# HOMER3E-V3_5-G510.net
KiCad netlist of a schematic drawn in Altium Designer
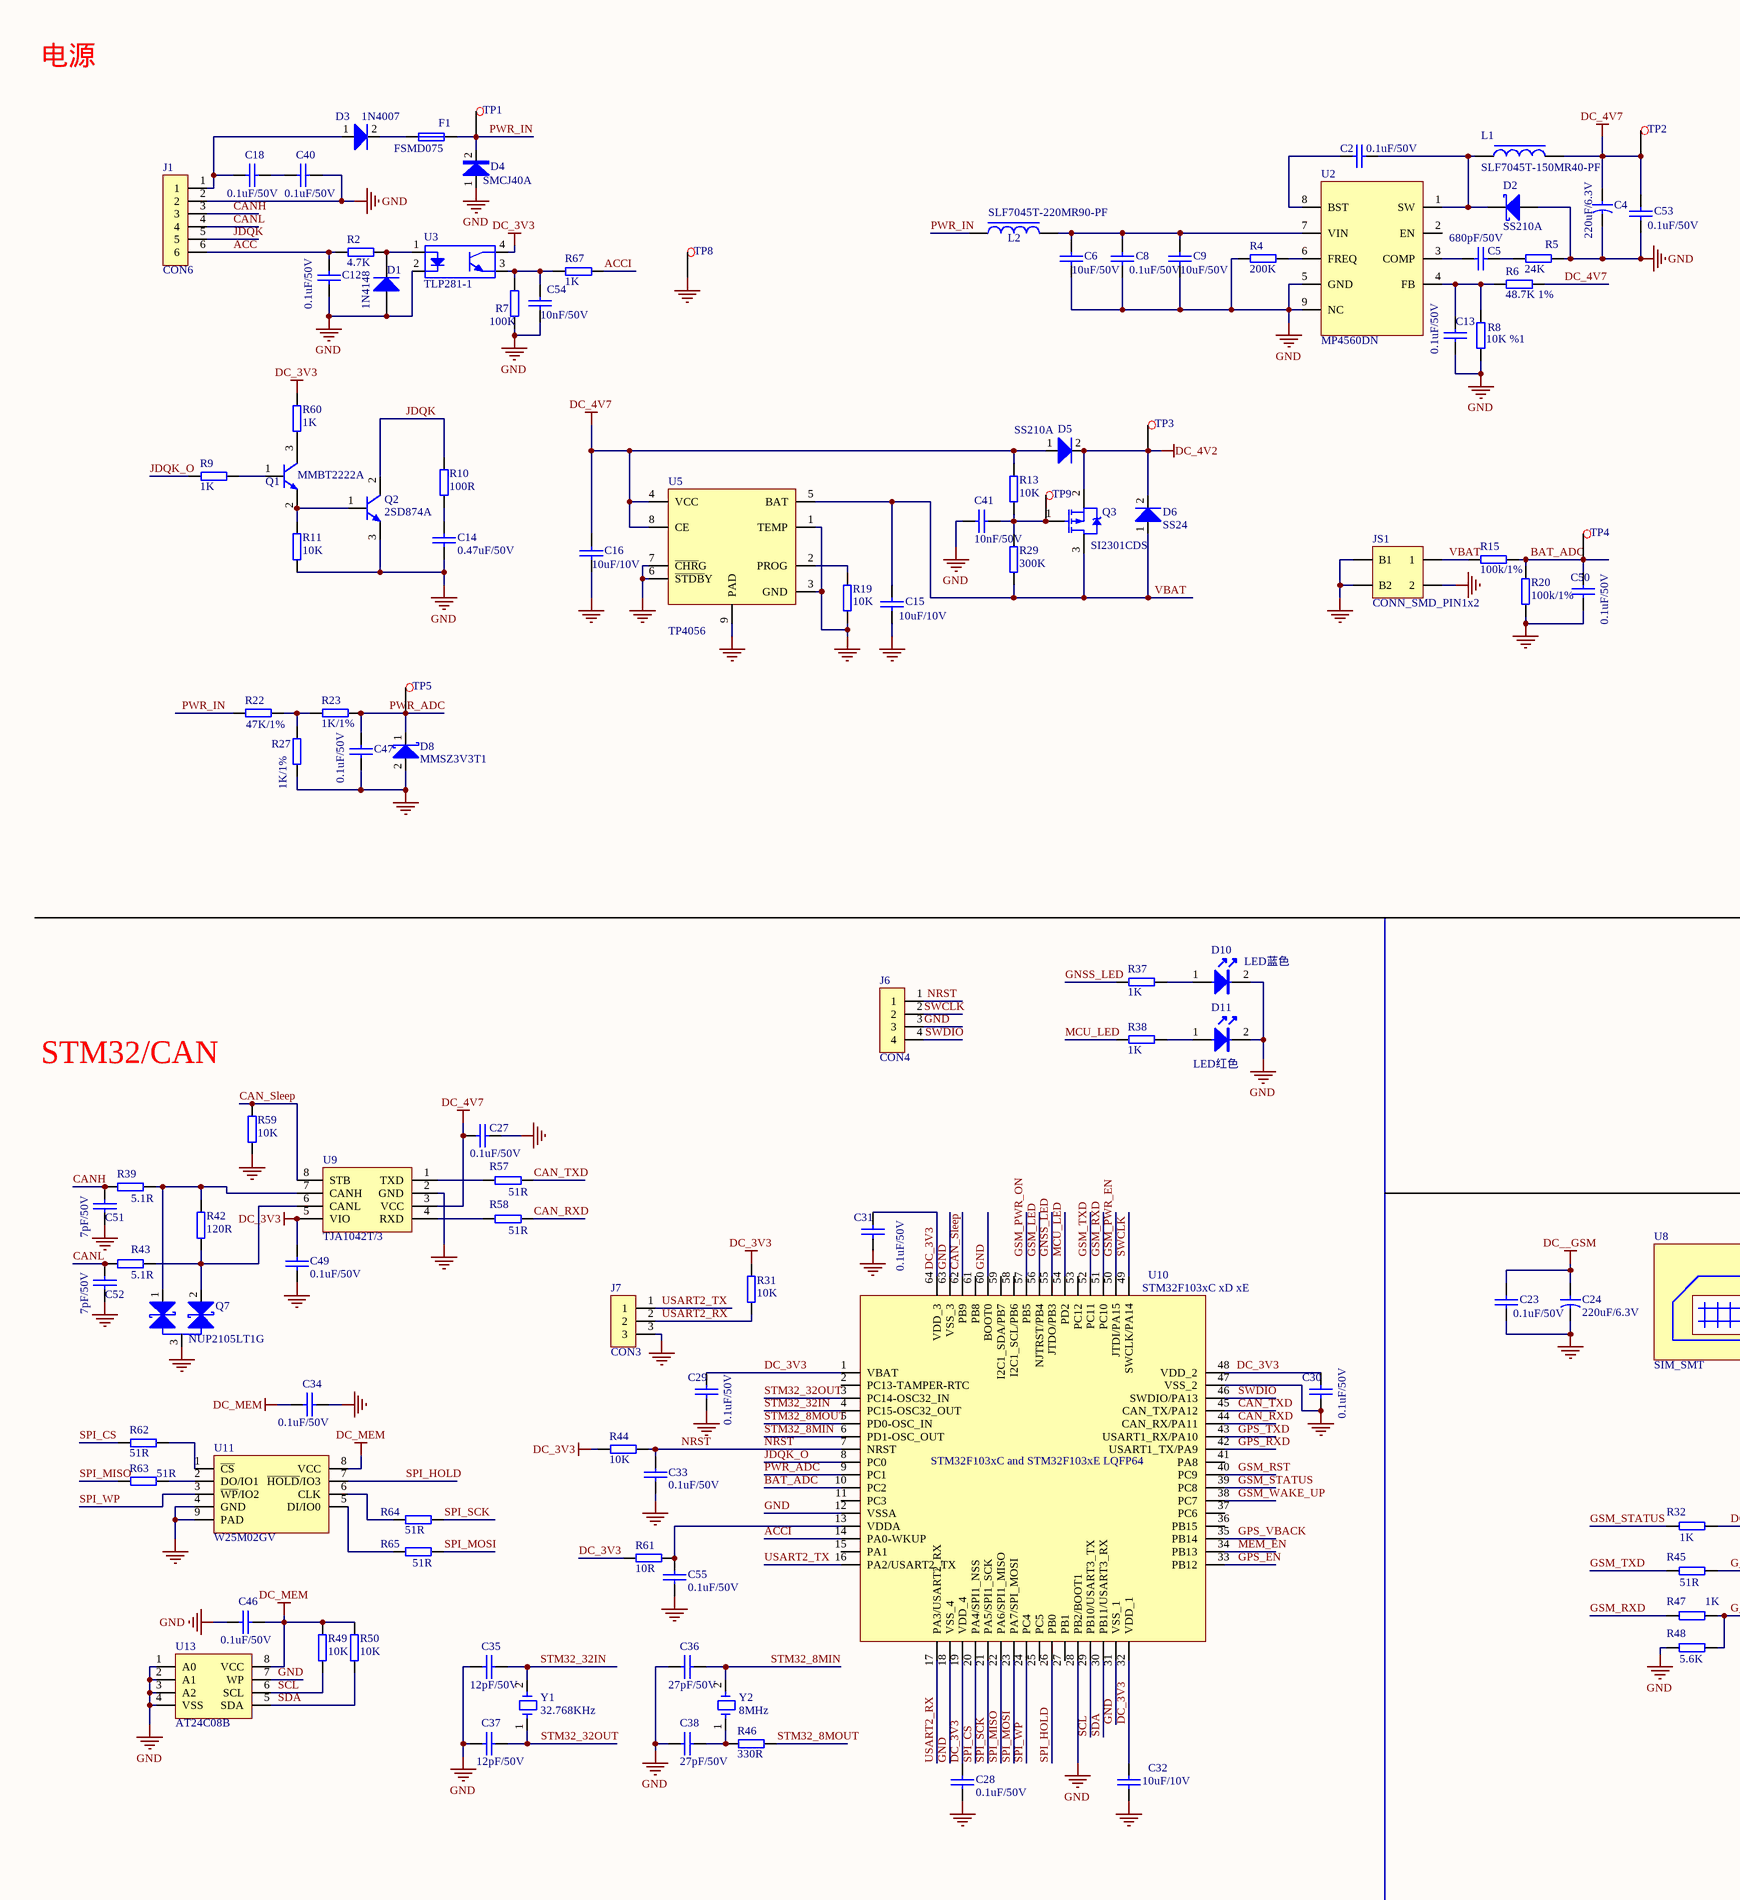
[diagram p0: HOMER3E-V3.5-G510.SchDoc, left]
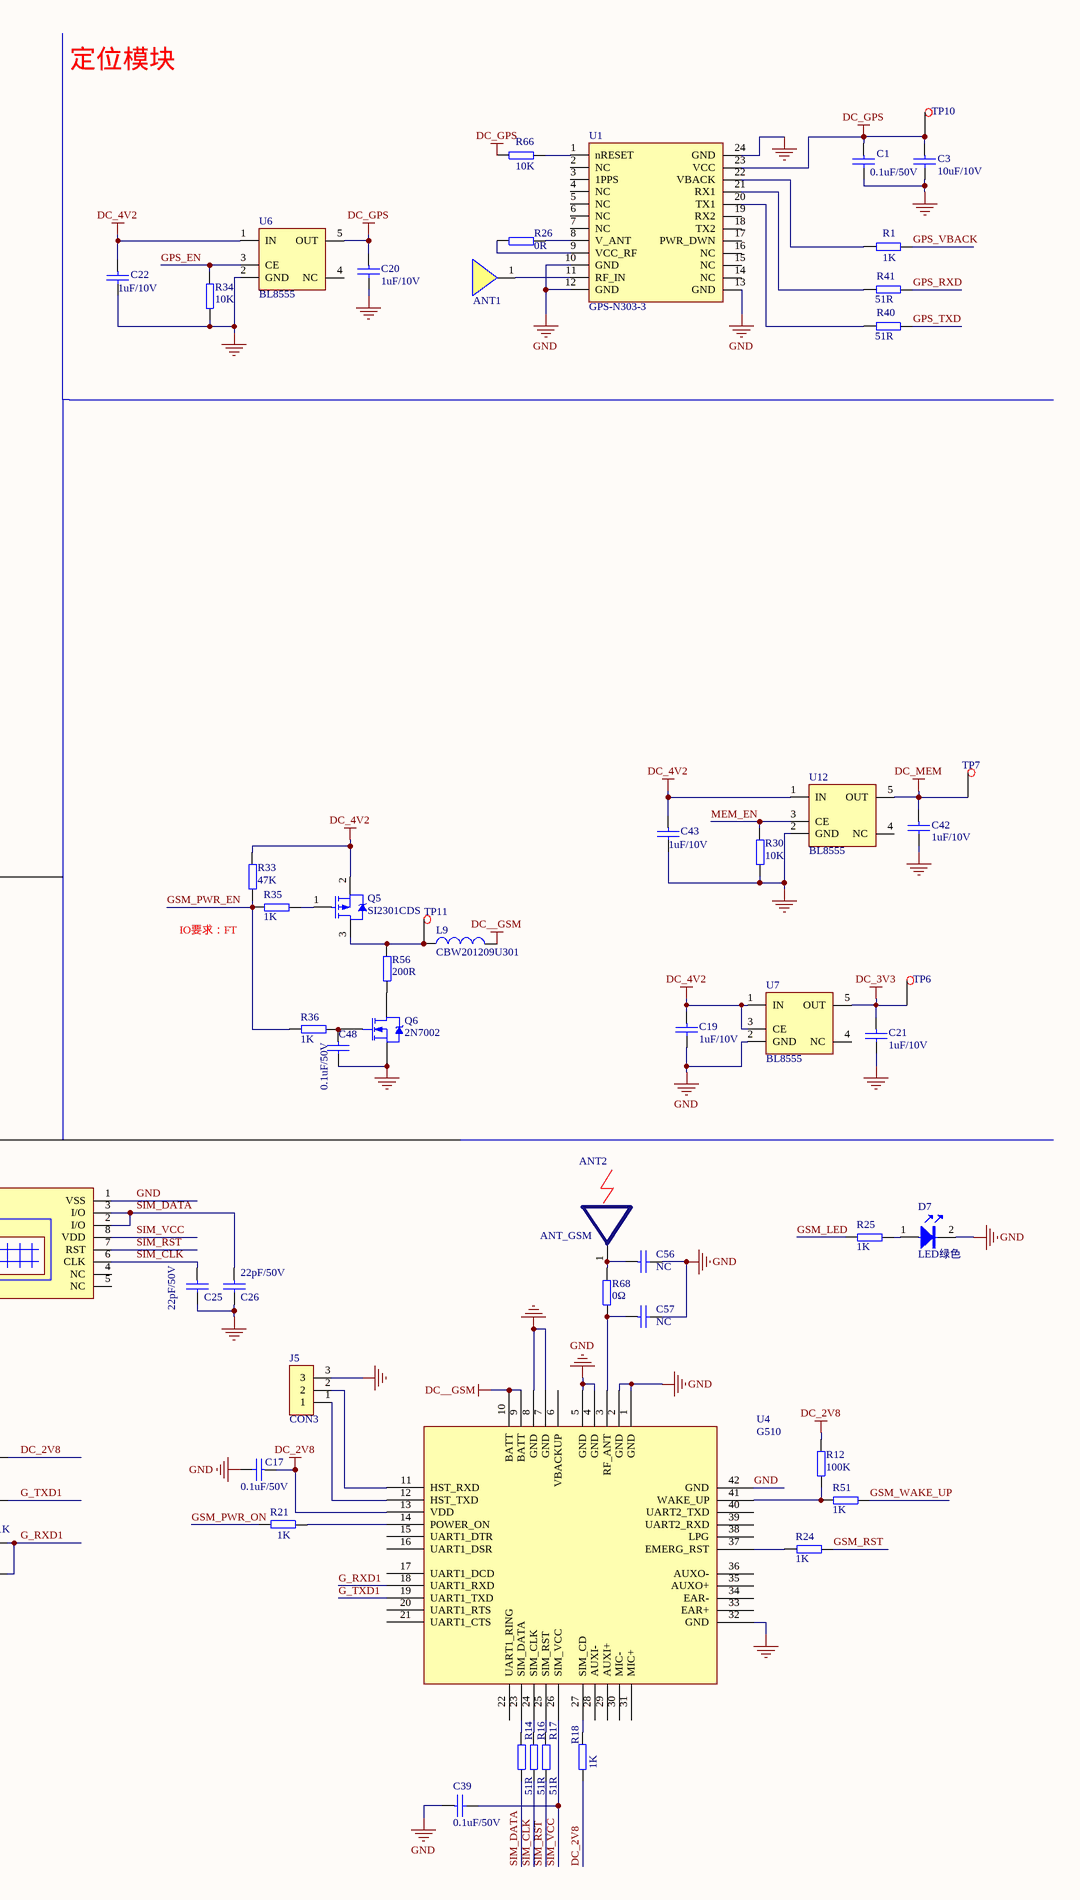
[diagram p1: HOMER3E-V3.5-G510.SchDoc, right]

(export (version "E")
  (design (tool "Eeschema 10.0.6"))
  (components
    (comp (ref "ANT1") (value "ANT") (footprint "GPS_ANT_25*25") (libsource (lib "AltiumLib") (part "ANT")))
    (comp (ref "ANT2") (value "ANT_GSM") (footprint "GSM_ANT") (libsource (lib "AltiumLib") (part "ANT_GSM")))
    (comp (ref "C1")
      (value "0.1uF/50V")
      (footprint "0603")
      (description "Capacitor")
      (libsource (lib "AltiumLib") (part "CAP"))
    )
    (comp (ref "C2")
      (value "0.1uF/50V")
      (footprint "0603")
      (description "Capacitor")
      (libsource (lib "AltiumLib") (part "CAP"))
    )
    (comp (ref "C3")
      (value "10uF/10V")
      (footprint "0603")
      (description "Capacitor")
      (libsource (lib "AltiumLib") (part "CAP"))
    )
    (comp (ref "C4")
      (value "220uF/6.3V")
      (footprint "7343")
      (description "Capacitor")
      (libsource (lib "AltiumLib") (part "Cap1"))
    )
    (comp (ref "C5")
      (value "680pF/50V")
      (footprint "0603")
      (description "Capacitor")
      (libsource (lib "AltiumLib") (part "CAP"))
    )
    (comp (ref "C6")
      (value "10uF/50V")
      (footprint "1206")
      (description "Capacitor")
      (libsource (lib "AltiumLib") (part "CAP"))
    )
    (comp (ref "C8")
      (value "0.1uF/50V")
      (footprint "0805")
      (description "Capacitor")
      (libsource (lib "AltiumLib") (part "CAP"))
    )
    (comp (ref "C9")
      (value "10uF/50V")
      (footprint "1206")
      (description "Capacitor")
      (libsource (lib "AltiumLib") (part "CAP"))
    )
    (comp (ref "C12")
      (value "0.1uF/50V")
      (footprint "0805")
      (description "Capacitor")
      (libsource (lib "AltiumLib") (part "CAP"))
    )
    (comp (ref "C13")
      (value "0.1uF/50V")
      (footprint "0603")
      (description "Capacitor")
      (libsource (lib "AltiumLib") (part "CAP"))
    )
    (comp (ref "C14")
      (value "0.47uF/50V")
      (footprint "0805")
      (description "Capacitor")
      (libsource (lib "AltiumLib") (part "CAP"))
    )
    (comp (ref "C15")
      (value "10uF/10V")
      (footprint "0603")
      (description "Capacitor")
      (libsource (lib "AltiumLib") (part "CAP"))
    )
    (comp (ref "C16")
      (value "10uF/10V")
      (footprint "0603")
      (description "Capacitor")
      (libsource (lib "AltiumLib") (part "CAP"))
    )
    (comp (ref "C17")
      (value "0.1uF/50V")
      (footprint "0603")
      (description "Capacitor")
      (libsource (lib "AltiumLib") (part "CAP"))
    )
    (comp (ref "C18")
      (value "0.1uF/50V")
      (footprint "0805")
      (description "Capacitor")
      (libsource (lib "AltiumLib") (part "CAP"))
    )
    (comp (ref "C19")
      (value "1uF/10V")
      (footprint "0603")
      (description "Capacitor")
      (libsource (lib "AltiumLib") (part "CAP"))
    )
    (comp (ref "C20")
      (value "1uF/10V")
      (footprint "0603")
      (description "Capacitor")
      (libsource (lib "AltiumLib") (part "CAP"))
    )
    (comp (ref "C21")
      (value "1uF/10V")
      (footprint "0603")
      (description "Capacitor")
      (libsource (lib "AltiumLib") (part "CAP"))
    )
    (comp (ref "C22")
      (value "1uF/10V")
      (footprint "0603")
      (description "Capacitor")
      (libsource (lib "AltiumLib") (part "CAP"))
    )
    (comp (ref "C23")
      (value "0.1uF/50V")
      (footprint "0603")
      (description "Capacitor")
      (libsource (lib "AltiumLib") (part "CAP"))
    )
    (comp (ref "C24")
      (value "220uF/6.3V")
      (footprint "7343")
      (description "Capacitor")
      (libsource (lib "AltiumLib") (part "Cap1"))
    )
    (comp (ref "C25")
      (value "22pF/50V")
      (footprint "0603")
      (description "Capacitor")
      (libsource (lib "AltiumLib") (part "CAP"))
    )
    (comp (ref "C26")
      (value "22pF/50V")
      (footprint "0603")
      (description "Capacitor")
      (libsource (lib "AltiumLib") (part "CAP"))
    )
    (comp (ref "C27")
      (value "0.1uF/50V")
      (footprint "0603")
      (description "Capacitor")
      (libsource (lib "AltiumLib") (part "CAP"))
    )
    (comp (ref "C28")
      (value "0.1uF/50V")
      (footprint "0603")
      (description "Capacitor")
      (libsource (lib "AltiumLib") (part "CAP"))
    )
    (comp (ref "C29")
      (value "0.1uF/50V")
      (footprint "0603")
      (description "Capacitor")
      (libsource (lib "AltiumLib") (part "CAP"))
    )
    (comp (ref "C30")
      (value "0.1uF/50V")
      (footprint "0603")
      (description "Capacitor")
      (libsource (lib "AltiumLib") (part "CAP"))
    )
    (comp (ref "C31")
      (value "0.1uF/50V")
      (footprint "0603")
      (description "Capacitor")
      (libsource (lib "AltiumLib") (part "CAP"))
    )
    (comp (ref "C32")
      (value "10uF/10V")
      (footprint "0603")
      (description "Capacitor")
      (libsource (lib "AltiumLib") (part "CAP"))
    )
    (comp (ref "C33")
      (value "0.1uF/50V")
      (footprint "0603")
      (description "Capacitor")
      (libsource (lib "AltiumLib") (part "CAP"))
    )
    (comp (ref "C34")
      (value "0.1uF/50V")
      (footprint "0603")
      (description "Capacitor")
      (libsource (lib "AltiumLib") (part "CAP"))
    )
    (comp (ref "C35")
      (value "12pF/50V")
      (footprint "0603")
      (description "Capacitor")
      (libsource (lib "AltiumLib") (part "CAP"))
    )
    (comp (ref "C36")
      (value "27pF/50V")
      (footprint "0603")
      (description "Capacitor")
      (libsource (lib "AltiumLib") (part "CAP"))
    )
    (comp (ref "C37")
      (value "12pF/50V")
      (footprint "0603")
      (description "Capacitor")
      (libsource (lib "AltiumLib") (part "CAP"))
    )
    (comp (ref "C38")
      (value "27pF/50V")
      (footprint "0603")
      (description "Capacitor")
      (libsource (lib "AltiumLib") (part "CAP"))
    )
    (comp (ref "C39")
      (value "0.1uF/50V")
      (footprint "0603")
      (description "Capacitor")
      (libsource (lib "AltiumLib") (part "CAP"))
    )
    (comp (ref "C40")
      (value "0.1uF/50V")
      (footprint "0805")
      (description "Capacitor")
      (libsource (lib "AltiumLib") (part "CAP"))
    )
    (comp (ref "C41")
      (value "10nF/50V")
      (footprint "0603")
      (description "Capacitor")
      (libsource (lib "AltiumLib") (part "CAP"))
    )
    (comp (ref "C42")
      (value "1uF/10V")
      (footprint "0603")
      (description "Capacitor")
      (libsource (lib "AltiumLib") (part "CAP"))
    )
    (comp (ref "C43")
      (value "1uF/10V")
      (footprint "0603")
      (description "Capacitor")
      (libsource (lib "AltiumLib") (part "CAP"))
    )
    (comp (ref "C46")
      (value "0.1uF/50V")
      (footprint "0603")
      (description "Capacitor")
      (libsource (lib "AltiumLib") (part "CAP"))
    )
    (comp (ref "C47")
      (value "0.1uF/50V")
      (footprint "0603")
      (description "Capacitor")
      (libsource (lib "AltiumLib") (part "CAP"))
    )
    (comp (ref "C48")
      (value "0.1uF/50V")
      (footprint "0603")
      (description "Capacitor")
      (libsource (lib "*") (part "CAP"))
    )
    (comp (ref "C49")
      (value "0.1uF/50V")
      (footprint "0603")
      (description "Capacitor")
      (libsource (lib "AltiumLib") (part "CAP"))
    )
    (comp (ref "C50")
      (value "0.1uF/50V")
      (footprint "0603")
      (description "Capacitor")
      (libsource (lib "AltiumLib") (part "CAP"))
    )
    (comp (ref "C51")
      (value "7pF/50V")
      (footprint "0603")
      (description "Capacitor")
      (libsource (lib "*") (part "CAP"))
    )
    (comp (ref "C52")
      (value "7pF/50V")
      (footprint "0603")
      (description "Capacitor")
      (libsource (lib "*") (part "CAP"))
    )
    (comp (ref "C53")
      (value "0.1uF/50V")
      (footprint "0603")
      (description "Capacitor")
      (libsource (lib "AltiumLib") (part "CAP"))
    )
    (comp (ref "C54")
      (value "10nF/50V")
      (footprint "0603")
      (description "Capacitor")
      (libsource (lib "AltiumLib") (part "CAP"))
    )
    (comp (ref "C55")
      (value "0.1uF/50V")
      (footprint "0603")
      (description "Capacitor")
      (libsource (lib "AltiumLib") (part "CAP"))
    )
    (comp (ref "C56")
      (value "NC")
      (footprint "C0603")
      (description "Capacitor")
      (libsource (lib "AltiumLib") (part "CAP"))
    )
    (comp (ref "C57")
      (value "NC")
      (footprint "C0603")
      (description "Capacitor")
      (libsource (lib "AltiumLib") (part "CAP"))
    )
    (comp (ref "D1")
      (value "1N4148")
      (footprint "SOD-123")
      (description "Default Diode")
      (fields (field (name "PUBLISHER") "Altium Limited"))
      (libsource (lib "Miscellaneous Devices") (part "Diode"))
    )
    (comp (ref "D2")
      (value "SS210A")
      (footprint "DO-214AC")
      (description "Schottky Diode")
      (libsource (lib "AltiumLib") (part "B340A"))
    )
    (comp (ref "D3")
      (value "1N4007")
      (footprint "DO-214AC")
      (description "High Conductance Fast Diode")
      (libsource (lib "AltiumLib") (part "1N4007"))
    )
    (comp (ref "D4") (value "SMCJ40A") (footprint "SMCJ40A") (libsource (lib "AltiumLib") (part "SMCJ40A")))
    (comp (ref "D5")
      (value "SS210A")
      (footprint "DO-214AC")
      (description "High Conductance Fast Diode")
      (libsource (lib "AltiumLib") (part "1N4007"))
    )
    (comp (ref "D6")
      (value "SS24")
      (footprint "DO-214AC")
      (description "High Conductance Fast Diode")
      (libsource (lib "AltiumLib") (part "1N4007"))
    )
    (comp (ref "D7")
      (value "LED绿色")
      (footprint "0603_led")
      (description "LED")
      (libsource (lib "AltiumLib") (part "LED"))
    )
    (comp (ref "D8")
      (value "MMSZ3V3T1")
      (footprint "SOD-123")
      (description "TVS")
      (libsource (lib "AltiumLib") (part "MMSZ3V3T1"))
    )
    (comp (ref "D10")
      (value "LED蓝色")
      (footprint "0603_led")
      (description "LED")
      (libsource (lib "AltiumLib") (part "LED"))
    )
    (comp (ref "D11")
      (value "LED红色")
      (footprint "0603_led")
      (description "LED")
      (libsource (lib "AltiumLib") (part "LED"))
    )
    (comp (ref "F1")
      (value "FSMD075")
      (footprint "2920")
      (description "Fuse")
      (libsource (lib "AltiumLib") (part "Fuse"))
    )
    (comp (ref "J1") (value "CON6") (footprint "CON6") (libsource (lib "AltiumLib") (part "CON6")))
    (comp (ref "J5") (value "CON3") (footprint "PH-3(2.54)") (libsource (lib "") (part "CON3_1")))
    (comp (ref "J6") (value "CON4") (footprint "PH-4(2.54)") (libsource (lib "AltiumLib") (part "CON4")))
    (comp (ref "J7") (value "CON3") (footprint "PH-3(2.54)") (libsource (lib "AltiumLib") (part "CON3")))
    (comp (ref "JS1")
      (value "CONN_SMD_PIN1x2")
      (footprint "MOLEX_53261-0271")
      (libsource (lib "AltiumLib") (part "CONN_SMD_PIN1x2"))
    )
    (comp (ref "L1")
      (value "SLF7045T-150MR40-PF")
      (footprint "MURATA_7 X 7")
      (description "INDUCTOR")
      (libsource (lib "AltiumLib") (part "INDUCTOR_2"))
    )
    (comp (ref "L2")
      (value "SLF7045T-220MR90-PF")
      (footprint "MURATA_7 X 7")
      (description "Magnetic-Core Inductor")
      (libsource (lib "AltiumLib") (part "Inductor"))
    )
    (comp (ref "L9")
      (value "CBW201209U301")
      (footprint "0805")
      (description "Inductor")
      (fields (field (name "PUBLISHER") "Altium Limited"))
      (libsource (lib "*") (part "Inductor"))
    )
    (comp (ref "Q1")
      (value "MMBT2222A")
      (footprint "SOT23-3")
      (libsource (lib "AltiumLib") (part "MMBT2222A"))
    )
    (comp (ref "Q2")
      (value "2SD874A")
      (footprint "SOT-89-3L")
      (description "NPN General Purpose Amplifier")
      (libsource (lib "AltiumLib") (part "2SD874"))
    )
    (comp (ref "Q3")
      (value "SI2301CDS")
      (footprint "SOT23-3")
      (description "P-Channel Power MOSFET")
      (libsource (lib "AltiumLib") (part "AO3415A"))
    )
    (comp (ref "Q5") (value "SI2301CDS") (footprint "SOT23-3") (libsource (lib "*") (part "Si2301ADS")))
    (comp (ref "Q6")
      (value "2N7002")
      (footprint "SOT23-3")
      (description "N-Channel Power MOSFET")
      (fields (field (name "PUBLISHER") "Altium Limited"))
      (libsource (lib "*") (part "NMOS-2"))
    )
    (comp (ref "Q7")
      (value "NUP2105LT1G")
      (footprint "SOT23-3")
      (libsource (lib "AltiumLib") (part "NUP2105LT1G"))
    )
    (comp (ref "R1")
      (value "1K")
      (footprint "0603")
      (description "Resistor")
      (libsource (lib "AltiumLib") (part "Res"))
    )
    (comp (ref "R2")
      (value "4.7K")
      (footprint "0603")
      (description "Resistor")
      (libsource (lib "AltiumLib") (part "Res"))
    )
    (comp (ref "R4")
      (value "200K")
      (footprint "0603")
      (description "Resistor")
      (libsource (lib "AltiumLib") (part "Res"))
    )
    (comp (ref "R5")
      (value "24K")
      (footprint "0603")
      (description "Resistor")
      (libsource (lib "AltiumLib") (part "Res"))
    )
    (comp (ref "R6")
      (value "48.7K 1%")
      (footprint "0603")
      (description "Resistor")
      (libsource (lib "AltiumLib") (part "Res"))
    )
    (comp (ref "R7")
      (value "100K")
      (footprint "0603")
      (description "Resistor")
      (libsource (lib "AltiumLib") (part "Res"))
    )
    (comp (ref "R8")
      (value "10K %1")
      (footprint "0603")
      (description "Resistor")
      (libsource (lib "AltiumLib") (part "Res"))
    )
    (comp (ref "R9")
      (value "1K")
      (footprint "0603")
      (description "Resistor")
      (libsource (lib "AltiumLib") (part "Res"))
    )
    (comp (ref "R10")
      (value "100R")
      (footprint "0805")
      (description "Resistor")
      (libsource (lib "AltiumLib") (part "Res"))
    )
    (comp (ref "R11")
      (value "10K")
      (footprint "0603")
      (description "Resistor")
      (libsource (lib "AltiumLib") (part "Res"))
    )
    (comp (ref "R12")
      (value "100K")
      (footprint "0603")
      (description "Resistor")
      (libsource (lib "AltiumLib") (part "Res"))
    )
    (comp (ref "R13")
      (value "10K")
      (footprint "0603")
      (description "Resistor")
      (libsource (lib "AltiumLib") (part "Res"))
    )
    (comp (ref "R14")
      (value "51R")
      (footprint "0603")
      (description "Resistor")
      (libsource (lib "AltiumLib") (part "Res"))
    )
    (comp (ref "R15")
      (value "100k/1%")
      (footprint "0603")
      (description "Resistor")
      (libsource (lib "AltiumLib") (part "Res"))
    )
    (comp (ref "R16")
      (value "51R")
      (footprint "0603")
      (description "Resistor")
      (libsource (lib "AltiumLib") (part "Res"))
    )
    (comp (ref "R17")
      (value "51R")
      (footprint "0603")
      (description "Resistor")
      (libsource (lib "AltiumLib") (part "Res"))
    )
    (comp (ref "R18") (value "1K") (footprint "0603") (libsource (lib "*") (part "RES_0603")))
    (comp (ref "R19")
      (value "10K")
      (footprint "0603")
      (description "Resistor")
      (libsource (lib "AltiumLib") (part "Res"))
    )
    (comp (ref "R20")
      (value "100k/1%")
      (footprint "0603")
      (description "Resistor")
      (libsource (lib "AltiumLib") (part "Res"))
    )
    (comp (ref "R21")
      (value "1K")
      (footprint "0603")
      (description "Resistor")
      (libsource (lib "AltiumLib") (part "Res"))
    )
    (comp (ref "R22")
      (value "47K/1%")
      (footprint "0603")
      (description "Resistor")
      (libsource (lib "AltiumLib") (part "Res"))
    )
    (comp (ref "R23")
      (value "1K/1%")
      (footprint "0603")
      (description "Resistor")
      (libsource (lib "AltiumLib") (part "Res"))
    )
    (comp (ref "R24")
      (value "1K")
      (footprint "0603")
      (description "Resistor")
      (libsource (lib "AltiumLib") (part "Res"))
    )
    (comp (ref "R25")
      (value "1K")
      (footprint "0603")
      (description "Resistor")
      (libsource (lib "AltiumLib") (part "Res"))
    )
    (comp (ref "R26")
      (value "0R")
      (footprint "0603")
      (description "Resistor")
      (libsource (lib "AltiumLib") (part "Res"))
    )
    (comp (ref "R27")
      (value "1K/1%")
      (footprint "0603")
      (description "Resistor")
      (libsource (lib "AltiumLib") (part "Res"))
    )
    (comp (ref "R29")
      (value "300K")
      (footprint "0603")
      (description "Resistor")
      (libsource (lib "AltiumLib") (part "Res"))
    )
    (comp (ref "R30")
      (value "10K")
      (footprint "0603")
      (description "Resistor")
      (libsource (lib "AltiumLib") (part "Res"))
    )
    (comp (ref "R31")
      (value "10K")
      (footprint "0603")
      (description "Resistor")
      (libsource (lib "AltiumLib") (part "Res"))
    )
    (comp (ref "R32")
      (value "1K")
      (footprint "0603")
      (description "Resistor")
      (libsource (lib "AltiumLib") (part "Res"))
    )
    (comp (ref "R33")
      (value "47K")
      (footprint "0603")
      (description "Resistor")
      (libsource (lib "*") (part "Res"))
    )
    (comp (ref "R34")
      (value "10K")
      (footprint "0603")
      (description "Resistor")
      (libsource (lib "AltiumLib") (part "Res"))
    )
    (comp (ref "R35")
      (value "1K")
      (footprint "0603")
      (description "Resistor")
      (libsource (lib "*") (part "Res"))
    )
    (comp (ref "R36")
      (value "1K")
      (footprint "0603")
      (description "Resistor")
      (libsource (lib "*") (part "Res"))
    )
    (comp (ref "R37")
      (value "1K")
      (footprint "0603")
      (description "Resistor")
      (libsource (lib "AltiumLib") (part "Res"))
    )
    (comp (ref "R38")
      (value "1K")
      (footprint "0603")
      (description "Resistor")
      (libsource (lib "AltiumLib") (part "Res"))
    )
    (comp (ref "R39")
      (value "5.1R")
      (footprint "0603")
      (description "Resistor")
      (libsource (lib "AltiumLib") (part "Res"))
    )
    (comp (ref "R40")
      (value "51R")
      (footprint "0603")
      (description "Resistor")
      (libsource (lib "AltiumLib") (part "Res"))
    )
    (comp (ref "R41")
      (value "51R")
      (footprint "0603")
      (description "Resistor")
      (libsource (lib "AltiumLib") (part "Res"))
    )
    (comp (ref "R42")
      (value "120R")
      (footprint "0805")
      (description "Resistor")
      (libsource (lib "AltiumLib") (part "Res"))
    )
    (comp (ref "R43")
      (value "5.1R")
      (footprint "0603")
      (description "Resistor")
      (libsource (lib "AltiumLib") (part "Res"))
    )
    (comp (ref "R44")
      (value "10K")
      (footprint "0603")
      (description "Resistor")
      (libsource (lib "AltiumLib") (part "Res"))
    )
    (comp (ref "R45")
      (value "51R")
      (footprint "0603")
      (description "Resistor")
      (libsource (lib "AltiumLib") (part "Res"))
    )
    (comp (ref "R46")
      (value "330R")
      (footprint "0603")
      (description "Resistor")
      (libsource (lib "AltiumLib") (part "Res"))
    )
    (comp (ref "R47")
      (value "1K")
      (footprint "0603")
      (description "Resistor")
      (libsource (lib "AltiumLib") (part "Res"))
    )
    (comp (ref "R48")
      (value "5.6K")
      (footprint "0603")
      (description "Resistor")
      (libsource (lib "AltiumLib") (part "Res"))
    )
    (comp (ref "R49")
      (value "10K")
      (footprint "0603")
      (description "Resistor")
      (libsource (lib "AltiumLib") (part "Res"))
    )
    (comp (ref "R50")
      (value "10K")
      (footprint "0603")
      (description "Resistor")
      (libsource (lib "AltiumLib") (part "Res"))
    )
    (comp (ref "R51")
      (value "1K")
      (footprint "0603")
      (description "Resistor")
      (libsource (lib "AltiumLib") (part "Res"))
    )
    (comp (ref "R56")
      (value "200R")
      (footprint "0805")
      (description "Resistor")
      (libsource (lib "*") (part "Res"))
    )
    (comp (ref "R57")
      (value "51R")
      (footprint "0603")
      (description "Resistor")
      (libsource (lib "AltiumLib") (part "Res"))
    )
    (comp (ref "R58")
      (value "51R")
      (footprint "0603")
      (description "Resistor")
      (libsource (lib "AltiumLib") (part "Res"))
    )
    (comp (ref "R59")
      (value "10K")
      (footprint "0603")
      (description "Resistor")
      (libsource (lib "AltiumLib") (part "Res"))
    )
    (comp (ref "R60")
      (value "1K")
      (footprint "0603")
      (description "Resistor")
      (libsource (lib "AltiumLib") (part "Res"))
    )
    (comp (ref "R61")
      (value "10R")
      (footprint "0603")
      (description "Resistor")
      (libsource (lib "AltiumLib") (part "Res"))
    )
    (comp (ref "R62")
      (value "51R")
      (footprint "0603")
      (description "Resistor")
      (libsource (lib "AltiumLib") (part "Res"))
    )
    (comp (ref "R63")
      (value "51R")
      (footprint "0603")
      (description "Resistor")
      (libsource (lib "AltiumLib") (part "Res"))
    )
    (comp (ref "R64")
      (value "51R")
      (footprint "0603")
      (description "Resistor")
      (libsource (lib "AltiumLib") (part "Res"))
    )
    (comp (ref "R65")
      (value "51R")
      (footprint "0603")
      (description "Resistor")
      (libsource (lib "AltiumLib") (part "Res"))
    )
    (comp (ref "R66")
      (value "10K")
      (footprint "0603")
      (description "Resistor")
      (libsource (lib "AltiumLib") (part "Res"))
    )
    (comp (ref "R67")
      (value "1K")
      (footprint "0603")
      (description "Resistor")
      (libsource (lib "AltiumLib") (part "Res"))
    )
    (comp (ref "R68")
      (value "0Ω")
      (footprint "R0603")
      (description "Resistor")
      (libsource (lib "AltiumLib") (part "Res"))
    )
    (comp (ref "TP1")
      (value "TestPoint")
      (footprint "TESTPOINT")
      (libsource (lib "AD SCH器件库") (part "TestPoint"))
    )
    (comp (ref "TP2")
      (value "TestPoint")
      (footprint "TESTPOINT")
      (libsource (lib "AD SCH器件库") (part "TestPoint"))
    )
    (comp (ref "TP3")
      (value "TestPoint")
      (footprint "TESTPOINT")
      (libsource (lib "AD SCH器件库") (part "TestPoint"))
    )
    (comp (ref "TP4")
      (value "TestPoint")
      (footprint "TESTPOINT")
      (libsource (lib "AD SCH器件库") (part "TestPoint"))
    )
    (comp (ref "TP5")
      (value "TestPoint")
      (footprint "TESTPOINT")
      (libsource (lib "AD SCH器件库") (part "TestPoint"))
    )
    (comp (ref "TP6")
      (value "TestPoint")
      (footprint "TESTPOINT")
      (libsource (lib "AD SCH器件库") (part "TestPoint"))
    )
    (comp (ref "TP7")
      (value "TestPoint")
      (footprint "TESTPOINT")
      (libsource (lib "AD SCH器件库") (part "TestPoint"))
    )
    (comp (ref "TP8")
      (value "TestPoint")
      (footprint "TESTPOINT")
      (libsource (lib "AD SCH器件库") (part "TestPoint"))
    )
    (comp (ref "TP9")
      (value "TestPoint")
      (footprint "TESTPOINT")
      (libsource (lib "AD SCH器件库") (part "TestPoint"))
    )
    (comp (ref "TP10") (value "TestPoint") (libsource (lib "AD SCH器件库") (part "TestPoint")))
    (comp (ref "TP11") (value "TestPoint") (libsource (lib "AD SCH器件库") (part "TestPoint")))
    (comp (ref "U1")
      (value "GPS-N303-3")
      (footprint "N303-3")
      (libsource (lib "AD SCH器件库") (part "GPS-N303-3"))
    )
    (comp (ref "U2")
      (value "MP4560DN")
      (footprint "MP4560DN_FOOTPRINT")
      (libsource (lib "AltiumLib") (part "MP4560DN"))
    )
    (comp (ref "U3")
      (value "TLP281-1")
      (footprint "tlp281")
      (description "光电耦合器")
      (libsource (lib "AltiumLib") (part "TLP281-1"))
    )
    (comp (ref "U4") (value "G510") (footprint "G510-Q50-20") (libsource (lib "AltiumLib") (part "G510")))
    (comp (ref "U5")
      (value "TP4056")
      (footprint "MP4560DN_FOOTPRINT")
      (libsource (lib "AltiumLib") (part "TP4056"))
    )
    (comp (ref "U6") (value "BL8555") (footprint "SOT23-5") (libsource (lib "AltiumLib") (part "BL8555")))
    (comp (ref "U7") (value "BL8555") (footprint "SOT23-5") (libsource (lib "AltiumLib") (part "BL8555")))
    (comp (ref "U8") (value "SIM_SMT") (footprint "SIM_SMT") (libsource (lib "AltiumLib") (part "SIM_SMT")))
    (comp (ref "U9") (value "TJA1042T/3") (footprint "SO-8") (libsource (lib "器件库") (part "TJA1042T/3")))
    (comp (ref "U10")
      (value "STM32F103xC xD xE")
      (footprint "TQFP-64")
      (libsource (lib "AltiumLib") (part "STM32F103xC xD xE"))
    )
    (comp (ref "U11")
      (value "W25M02GV")
      (footprint "WSON8X6-8")
      (libsource (lib "AltiumLib") (part "W25M02GV"))
    )
    (comp (ref "U12") (value "BL8555") (footprint "SOT23-5") (libsource (lib "AltiumLib") (part "BL8555")))
    (comp (ref "U13")
      (value "AT24C08B")
      (footprint "SO-8")
      (description "8K I2C CMOS Serial EEPROM")
      (libsource (lib "AltiumLib") (part "AT24C08B"))
    )
    (comp (ref "Y1")
      (value "32.768KHz")
      (footprint "XTAL_FC-135")
      (description "Crystal Oscillator")
      (libsource (lib "AltiumLib") (part "XTAL"))
    )
    (comp (ref "Y2")
      (value "8MHz")
      (footprint "XTAL_5032_2")
      (description "Crystal Oscillator")
      (libsource (lib "AltiumLib") (part "XTAL"))
    )
  )
  (nets
    (net (code "1") (name "/ACC") (class "Default")
      (node (ref "C12") (pin "1") (pinfunction "1_1") (pintype "passive"))
      (node (ref "J1") (pin "6") (pinfunction "6_6") (pintype "passive"))
      (node (ref "R2") (pin "2") (pinfunction "2_2") (pintype "passive"))
    )
    (net (code "2") (name "/ACCI") (class "Default")
      (node (ref "R67") (pin "2") (pinfunction "2_2") (pintype "passive"))
      (node (ref "U10") (pin "14") (pinfunction "PA0-WKUP_14") (pintype "passive"))
    )
    (net (code "3") (name "/BAT_ADC") (class "Default")
      (node (ref "C50") (pin "1") (pinfunction "1_1") (pintype "passive"))
      (node (ref "R15") (pin "1") (pinfunction "1_1") (pintype "passive"))
      (node (ref "R20") (pin "1") (pinfunction "1_1") (pintype "passive"))
      (node (ref "TP4") (pin "1") (pinfunction "1_1") (pintype "passive"))
      (node (ref "U10") (pin "10") (pinfunction "PC2_10") (pintype "passive"))
    )
    (net (code "4") (name "/CANH") (class "Default")
      (node (ref "C51") (pin "1") (pinfunction "1_1") (pintype "passive"))
      (node (ref "J1") (pin "3") (pinfunction "3_3") (pintype "passive"))
      (node (ref "R39") (pin "2") (pinfunction "2_2") (pintype "passive"))
    )
    (net (code "5") (name "/CANL") (class "Default")
      (node (ref "C52") (pin "1") (pinfunction "1_1") (pintype "passive"))
      (node (ref "J1") (pin "4") (pinfunction "4_4") (pintype "passive"))
      (node (ref "R43") (pin "2") (pinfunction "2_2") (pintype "passive"))
    )
    (net (code "6") (name "/CAN_RXD") (class "Default")
      (node (ref "R58") (pin "2") (pinfunction "2_2") (pintype "passive"))
      (node (ref "U10") (pin "44") (pinfunction "CAN_RX/PA11_44") (pintype "passive"))
    )
    (net (code "7") (name "/CAN_Sleep") (class "Default")
      (node (ref "R59") (pin "1") (pinfunction "1_1") (pintype "passive"))
      (node (ref "U10") (pin "62") (pinfunction "PB9_62") (pintype "passive"))
      (node (ref "U9") (pin "8") (pinfunction "STB_8") (pintype "passive"))
    )
    (net (code "8") (name "/CAN_TXD") (class "Default")
      (node (ref "R57") (pin "2") (pinfunction "2_2") (pintype "passive"))
      (node (ref "U10") (pin "45") (pinfunction "CAN_TX/PA12_45") (pintype "passive"))
    )
    (net (code "9") (name "/GNSS_LED") (class "Default")
      (node (ref "R37") (pin "1") (pinfunction "1_1") (pintype "passive"))
      (node (ref "U10") (pin "55") (pinfunction "JTDO/PB3_55") (pintype "passive"))
    )
    (net (code "10") (name "/GPS_EN") (class "Default")
      (node (ref "R34") (pin "1") (pinfunction "1_1") (pintype "passive"))
      (node (ref "U10") (pin "33") (pinfunction "PB12_33") (pintype "passive"))
      (node (ref "U6") (pin "3") (pinfunction "CE_3") (pintype "passive"))
    )
    (net (code "11") (name "/GPS_RXD") (class "Default")
      (node (ref "R41") (pin "1") (pinfunction "1_1") (pintype "passive"))
      (node (ref "U10") (pin "42") (pinfunction "USART1_TX/PA9_42") (pintype "passive"))
    )
    (net (code "12") (name "/GPS_TXD") (class "Default")
      (node (ref "R40") (pin "1") (pinfunction "1_1") (pintype "passive"))
      (node (ref "U10") (pin "43") (pinfunction "USART1_RX/PA10_43") (pintype "passive"))
    )
    (net (code "13") (name "/GPS_VBACK") (class "Default")
      (node (ref "R1") (pin "1") (pinfunction "1_1") (pintype "passive"))
      (node (ref "U10") (pin "35") (pinfunction "PB14_35") (pintype "passive"))
    )
    (net (code "14") (name "/GSM_LED") (class "Default")
      (node (ref "R25") (pin "1") (pinfunction "1_1") (pintype "passive"))
      (node (ref "U10") (pin "56") (pinfunction "NJTRST/PB4_56") (pintype "passive"))
    )
    (net (code "15") (name "/GSM_PWR_EN") (class "Default")
      (node (ref "R33") (pin "2") (pinfunction "2_2") (pintype "passive"))
      (node (ref "R35") (pin "1") (pinfunction "1_1") (pintype "passive"))
      (node (ref "R36") (pin "2") (pinfunction "2_2") (pintype "passive"))
      (node (ref "U10") (pin "50") (pinfunction "JTDI/PA15_50") (pintype "passive"))
    )
    (net (code "16") (name "/GSM_PWR_ON") (class "Default")
      (node (ref "R21") (pin "2") (pinfunction "2_2") (pintype "passive"))
      (node (ref "U10") (pin "57") (pinfunction "PB5_57") (pintype "passive"))
    )
    (net (code "17") (name "/GSM_RST") (class "Default")
      (node (ref "R24") (pin "2") (pinfunction "2_2") (pintype "passive"))
      (node (ref "U10") (pin "40") (pinfunction "PC9_40") (pintype "passive"))
    )
    (net (code "18") (name "/GSM_RXD") (class "Default")
      (node (ref "R47") (pin "2") (pinfunction "2_2") (pintype "passive"))
      (node (ref "U10") (pin "51") (pinfunction "PC10_51") (pintype "passive"))
    )
    (net (code "19") (name "/GSM_STATUS") (class "Default")
      (node (ref "R32") (pin "2") (pinfunction "2_2") (pintype "passive"))
      (node (ref "U10") (pin "39") (pinfunction "PC8_39") (pintype "passive"))
    )
    (net (code "20") (name "/GSM_TXD") (class "Default")
      (node (ref "R45") (pin "2") (pinfunction "2_2") (pintype "passive"))
      (node (ref "U10") (pin "52") (pinfunction "PC11_52") (pintype "passive"))
    )
    (net (code "21") (name "/GSM_WAKE_UP") (class "Default")
      (node (ref "R51") (pin "2") (pinfunction "2_2") (pintype "passive"))
      (node (ref "U10") (pin "38") (pinfunction "PC7_38") (pintype "passive"))
    )
    (net (code "22") (name "/G_RXD1") (class "Default")
      (node (ref "R47") (pin "1") (pinfunction "1_1") (pintype "passive"))
      (node (ref "R48") (pin "1") (pinfunction "1_1") (pintype "passive"))
      (node (ref "U4") (pin "18") (pinfunction "UART1_RXD_18") (pintype "passive"))
    )
    (net (code "23") (name "/G_TXD1") (class "Default")
      (node (ref "R45") (pin "1") (pinfunction "1_1") (pintype "passive"))
      (node (ref "U4") (pin "19") (pinfunction "UART1_TXD_19") (pintype "passive"))
    )
    (net (code "24") (name "/JDQK") (class "Default")
      (node (ref "J1") (pin "5") (pinfunction "5_5") (pintype "passive"))
      (node (ref "Q2") (pin "2") (pinfunction "B_2") (pintype "passive"))
      (node (ref "R10") (pin "1") (pinfunction "1_1") (pintype "passive"))
    )
    (net (code "25") (name "/JDQK_O") (class "Default")
      (node (ref "R9") (pin "1") (pinfunction "1_1") (pintype "passive"))
      (node (ref "U10") (pin "8") (pinfunction "PC0_8") (pintype "passive"))
    )
    (net (code "26") (name "/MCU_LED") (class "Default")
      (node (ref "R38") (pin "2") (pinfunction "2_2") (pintype "passive"))
      (node (ref "U10") (pin "54") (pinfunction "PD2_54") (pintype "passive"))
    )
    (net (code "27") (name "/MEM_EN") (class "Default")
      (node (ref "R30") (pin "1") (pinfunction "1_1") (pintype "passive"))
      (node (ref "U10") (pin "34") (pinfunction "PB13_34") (pintype "passive"))
      (node (ref "U12") (pin "3") (pinfunction "CE_3") (pintype "passive"))
    )
    (net (code "28") (name "/NRST") (class "Default")
      (node (ref "C33") (pin "1") (pinfunction "1_1") (pintype "passive"))
      (node (ref "J6") (pin "1") (pinfunction "1_1") (pintype "passive"))
      (node (ref "R44") (pin "1") (pinfunction "1_1") (pintype "passive"))
      (node (ref "U10") (pin "7") (pinfunction "NRST_7") (pintype "passive"))
    )
    (net (code "29") (name "/PWR_ADC") (class "Default")
      (node (ref "C47") (pin "1") (pinfunction "1_1") (pintype "passive"))
      (node (ref "D8") (pin "1") (pinfunction "K_1") (pintype "passive"))
      (node (ref "R23") (pin "1") (pinfunction "1_1") (pintype "passive"))
      (node (ref "TP5") (pin "1") (pinfunction "1_1") (pintype "passive"))
      (node (ref "U10") (pin "9") (pinfunction "PC1_9") (pintype "passive"))
    )
    (net (code "30") (name "/PWR_IN") (class "Default")
      (node (ref "D4") (pin "2") (pinfunction "K_2") (pintype "passive"))
      (node (ref "F1") (pin "2") (pinfunction "2_2") (pintype "passive"))
      (node (ref "L2") (pin "1") (pinfunction "1_1") (pintype "passive"))
      (node (ref "R22") (pin "2") (pinfunction "2_2") (pintype "passive"))
      (node (ref "TP1") (pin "1") (pinfunction "1_1") (pintype "passive"))
    )
    (net (code "31") (name "/SCL") (class "Default")
      (node (ref "R49") (pin "2") (pinfunction "2_2") (pintype "passive"))
      (node (ref "U10") (pin "29") (pinfunction "PB10/USART3_TX_29") (pintype "passive"))
      (node (ref "U13") (pin "6") (pinfunction "SCL_6") (pintype "passive"))
    )
    (net (code "32") (name "/SDA") (class "Default")
      (node (ref "R50") (pin "2") (pinfunction "2_2") (pintype "passive"))
      (node (ref "U10") (pin "30") (pinfunction "PB11/USART3_RX_30") (pintype "passive"))
      (node (ref "U13") (pin "5") (pinfunction "SDA_5") (pintype "passive"))
    )
    (net (code "33") (name "/SIM_CLK") (class "Default")
      (node (ref "C25") (pin "1") (pinfunction "1_1") (pintype "passive"))
      (node (ref "R16") (pin "2") (pinfunction "2_2") (pintype "passive"))
      (node (ref "U8") (pin "6") (pinfunction "CLK_6") (pintype "passive"))
    )
    (net (code "34") (name "/SIM_DATA") (class "Default")
      (node (ref "C26") (pin "1") (pinfunction "1_1") (pintype "passive"))
      (node (ref "R14") (pin "2") (pinfunction "2_2") (pintype "passive"))
      (node (ref "U8") (pin "2") (pinfunction "I/O_2") (pintype "passive"))
      (node (ref "U8") (pin "3") (pinfunction "I/O_3") (pintype "passive"))
    )
    (net (code "35") (name "/SIM_RST") (class "Default")
      (node (ref "R17") (pin "2") (pinfunction "2_2") (pintype "passive"))
      (node (ref "U8") (pin "7") (pinfunction "RST_7") (pintype "passive"))
    )
    (net (code "36") (name "/SIM_VCC") (class "Default")
      (node (ref "C39") (pin "2") (pinfunction "2_2") (pintype "passive"))
      (node (ref "U4") (pin "26") (pinfunction "SIM_VCC_26") (pintype "passive"))
      (node (ref "U8") (pin "8") (pinfunction "VDD_8") (pintype "passive"))
    )
    (net (code "37") (name "/SPI_CS") (class "Default")
      (node (ref "R62") (pin "1") (pinfunction "1_1") (pintype "passive"))
      (node (ref "U10") (pin "20") (pinfunction "PA4/SPI1_NSS_20") (pintype "passive"))
    )
    (net (code "38") (name "/SPI_HOLD") (class "Default")
      (node (ref "U10") (pin "26") (pinfunction "PB0_26") (pintype "passive"))
      (node (ref "U11") (pin "7") (pinfunction "~{HOLD}/IO3_7") (pintype "passive"))
    )
    (net (code "39") (name "/SPI_MISO") (class "Default")
      (node (ref "R63") (pin "1") (pinfunction "1_1") (pintype "passive"))
      (node (ref "U10") (pin "22") (pinfunction "PA6/SPI1_MISO_22") (pintype "passive"))
    )
    (net (code "40") (name "/SPI_MOSI") (class "Default")
      (node (ref "R65") (pin "2") (pinfunction "2_2") (pintype "passive"))
      (node (ref "U10") (pin "23") (pinfunction "PA7/SPI_MOSI_23") (pintype "passive"))
    )
    (net (code "41") (name "/SPI_SCK") (class "Default")
      (node (ref "R64") (pin "2") (pinfunction "2_2") (pintype "passive"))
      (node (ref "U10") (pin "21") (pinfunction "PA5/SPI1_SCK_21") (pintype "passive"))
    )
    (net (code "42") (name "/SPI_WP") (class "Default")
      (node (ref "U10") (pin "24") (pinfunction "PC4_24") (pintype "passive"))
      (node (ref "U11") (pin "3") (pinfunction "~{WP}/IO2_3") (pintype "passive"))
    )
    (net (code "43") (name "/STM32_8MIN") (class "Default")
      (node (ref "C36") (pin "2") (pinfunction "2_2") (pintype "passive"))
      (node (ref "U10") (pin "6") (pinfunction "PD1-OSC_OUT_6") (pintype "passive"))
      (node (ref "Y2") (pin "2") (pinfunction "OSC2_2") (pintype "passive"))
    )
    (net (code "44") (name "/STM32_8MOUT") (class "Default")
      (node (ref "R46") (pin "2") (pinfunction "2_2") (pintype "passive"))
      (node (ref "U10") (pin "5") (pinfunction "PD0-OSC_IN_5") (pintype "passive"))
    )
    (net (code "45") (name "/STM32_32IN") (class "Default")
      (node (ref "C35") (pin "2") (pinfunction "2_2") (pintype "passive"))
      (node (ref "U10") (pin "4") (pinfunction "PC15-OSC32_OUT_4") (pintype "passive"))
      (node (ref "Y1") (pin "2") (pinfunction "OSC2_2") (pintype "passive"))
    )
    (net (code "46") (name "/STM32_32OUT") (class "Default")
      (node (ref "C37") (pin "2") (pinfunction "2_2") (pintype "passive"))
      (node (ref "U10") (pin "3") (pinfunction "PC14-OSC32_IN_3") (pintype "passive"))
      (node (ref "Y1") (pin "1") (pinfunction "OSC1_1") (pintype "passive"))
    )
    (net (code "47") (name "/SWCLK") (class "Default")
      (node (ref "J6") (pin "2") (pinfunction "2_2") (pintype "passive"))
      (node (ref "U10") (pin "49") (pinfunction "SWCLK/PA14_49") (pintype "passive"))
    )
    (net (code "48") (name "/SWDIO") (class "Default")
      (node (ref "J6") (pin "4") (pinfunction "4_4") (pintype "passive"))
      (node (ref "U10") (pin "46") (pinfunction "SWDIO/PA13_46") (pintype "passive"))
    )
    (net (code "49") (name "/USART2_RX") (class "Default")
      (node (ref "J7") (pin "2") (pinfunction "2_2") (pintype "passive"))
      (node (ref "R31") (pin "2") (pinfunction "2_2") (pintype "passive"))
      (node (ref "U10") (pin "17") (pinfunction "PA3/USART2_RX_17") (pintype "passive"))
    )
    (net (code "50") (name "/USART2_TX") (class "Default")
      (node (ref "J7") (pin "1") (pinfunction "1_1") (pintype "passive"))
      (node (ref "U10") (pin "16") (pinfunction "PA2/USART2_TX_16") (pintype "passive"))
    )
    (net (code "51") (name "/VBAT") (class "Default")
      (node (ref "C15") (pin "1") (pinfunction "1_1") (pintype "passive"))
      (node (ref "D6") (pin "1") (pinfunction "A_1") (pintype "passive"))
      (node (ref "JS1") (pin "1") (pinfunction "1_1") (pintype "passive"))
      (node (ref "Q3") (pin "3") (pinfunction "S_3") (pintype "passive"))
      (node (ref "R15") (pin "2") (pinfunction "2_2") (pintype "passive"))
      (node (ref "R29") (pin "2") (pinfunction "2_2") (pintype "passive"))
      (node (ref "U5") (pin "5") (pinfunction "BAT_5") (pintype "passive"))
    )
    (net (code "52") (name "DC_2V8") (class "Default")
      (node (ref "C17") (pin "1") (pinfunction "1_1") (pintype "passive"))
      (node (ref "R12") (pin "1") (pinfunction "1_1") (pintype "passive"))
      (node (ref "R18") (pin "1") (pintype "passive"))
      (node (ref "R32") (pin "1") (pinfunction "1_1") (pintype "passive"))
      (node (ref "U4") (pin "13") (pinfunction "VDD_13") (pintype "passive"))
    )
    (net (code "53") (name "DC_3V3") (class "Default")
      (node (ref "C21") (pin "1") (pinfunction "1_1") (pintype "passive"))
      (node (ref "C28") (pin "1") (pinfunction "1_1") (pintype "passive"))
      (node (ref "C29") (pin "1") (pinfunction "1_1") (pintype "passive"))
      (node (ref "C30") (pin "1") (pinfunction "1_1") (pintype "passive"))
      (node (ref "C31") (pin "1") (pinfunction "1_1") (pintype "passive"))
      (node (ref "C32") (pin "1") (pinfunction "1_1") (pintype "passive"))
      (node (ref "C49") (pin "2") (pinfunction "2_2") (pintype "passive"))
      (node (ref "R31") (pin "1") (pinfunction "1_1") (pintype "passive"))
      (node (ref "R44") (pin "2") (pinfunction "2_2") (pintype "passive"))
      (node (ref "R60") (pin "2") (pinfunction "2_2") (pintype "passive"))
      (node (ref "R61") (pin "2") (pinfunction "2_2") (pintype "passive"))
      (node (ref "TP6") (pin "1") (pinfunction "1_1") (pintype "passive"))
      (node (ref "U10") (pin "1") (pinfunction "VBAT_1") (pintype "passive"))
      (node (ref "U10") (pin "19") (pinfunction "VDD_4_19") (pintype "passive"))
      (node (ref "U10") (pin "32") (pinfunction "VDD_1_32") (pintype "passive"))
      (node (ref "U10") (pin "48") (pinfunction "VDD_2_48") (pintype "passive"))
      (node (ref "U10") (pin "64") (pinfunction "VDD_3_64") (pintype "passive"))
      (node (ref "U3") (pin "4") (pinfunction "4_4") (pintype "passive"))
      (node (ref "U7") (pin "5") (pinfunction "OUT_5") (pintype "passive"))
      (node (ref "U9") (pin "5") (pinfunction "VIO_5") (pintype "passive"))
    )
    (net (code "54") (name "DC_4V2") (class "Default")
      (node (ref "C19") (pin "1") (pinfunction "1_1") (pintype "passive"))
      (node (ref "C22") (pin "1") (pinfunction "1_1") (pintype "passive"))
      (node (ref "C43") (pin "1") (pinfunction "1_1") (pintype "passive"))
      (node (ref "D5") (pin "2") (pinfunction "K_2") (pintype "passive"))
      (node (ref "D6") (pin "2") (pinfunction "K_2") (pintype "passive"))
      (node (ref "Q3") (pin "2") (pinfunction "D_2") (pintype "passive"))
      (node (ref "Q5") (pin "2") (pinfunction "D_2") (pintype "passive"))
      (node (ref "R33") (pin "1") (pinfunction "1_1") (pintype "passive"))
      (node (ref "TP3") (pin "1") (pinfunction "1_1") (pintype "passive"))
      (node (ref "U12") (pin "1") (pinfunction "IN_1") (pintype "passive"))
      (node (ref "U6") (pin "1") (pinfunction "IN_1") (pintype "passive"))
      (node (ref "U7") (pin "1") (pinfunction "IN_1") (pintype "passive"))
      (node (ref "U7") (pin "3") (pinfunction "CE_3") (pintype "passive"))
    )
    (net (code "55") (name "DC_4V7") (class "Default")
      (node (ref "C16") (pin "1") (pinfunction "1_1") (pintype "passive"))
      (node (ref "C27") (pin "1") (pinfunction "1_1") (pintype "passive"))
      (node (ref "C4") (pin "1") (pinfunction "1_1") (pintype "passive"))
      (node (ref "C53") (pin "1") (pinfunction "1_1") (pintype "passive"))
      (node (ref "D5") (pin "1") (pinfunction "A_1") (pintype "passive"))
      (node (ref "L1") (pin "2") (pinfunction "2_2") (pintype "passive"))
      (node (ref "R13") (pin "1") (pinfunction "1_1") (pintype "passive"))
      (node (ref "R6") (pin "1") (pinfunction "1_1") (pintype "passive"))
      (node (ref "TP2") (pin "1") (pinfunction "1_1") (pintype "passive"))
      (node (ref "U5") (pin "4") (pinfunction "VCC_4") (pintype "passive"))
      (node (ref "U5") (pin "8") (pinfunction "CE_8") (pintype "passive"))
      (node (ref "U9") (pin "3") (pinfunction "VCC_3") (pintype "passive"))
    )
    (net (code "56") (name "DC_GPS") (class "Default")
      (node (ref "C1") (pin "1") (pinfunction "1_1") (pintype "passive"))
      (node (ref "C20") (pin "1") (pinfunction "1_1") (pintype "passive"))
      (node (ref "C3") (pin "1") (pinfunction "1_1") (pintype "passive"))
      (node (ref "R66") (pin "1") (pinfunction "1_1") (pintype "passive"))
      (node (ref "TP10") (pin "1") (pinfunction "1_1") (pintype "passive"))
      (node (ref "U1") (pin "23") (pinfunction "VCC_23") (pintype "passive"))
      (node (ref "U6") (pin "5") (pinfunction "OUT_5") (pintype "passive"))
    )
    (net (code "57") (name "DC_MEM") (class "Default")
      (node (ref "C34") (pin "2") (pinfunction "2_2") (pintype "passive"))
      (node (ref "C42") (pin "1") (pinfunction "1_1") (pintype "passive"))
      (node (ref "C46") (pin "1") (pinfunction "1_1") (pintype "passive"))
      (node (ref "R49") (pin "1") (pinfunction "1_1") (pintype "passive"))
      (node (ref "R50") (pin "1") (pinfunction "1_1") (pintype "passive"))
      (node (ref "TP7") (pin "1") (pinfunction "1_1") (pintype "passive"))
      (node (ref "U11") (pin "8") (pinfunction "VCC_8") (pintype "passive"))
      (node (ref "U12") (pin "5") (pinfunction "OUT_5") (pintype "passive"))
      (node (ref "U13") (pin "8") (pinfunction "VCC_8") (pintype "power_in"))
    )
    (net (code "58") (name "DC__GSM") (class "Default")
      (node (ref "C23") (pin "1") (pinfunction "1_1") (pintype "passive"))
      (node (ref "C24") (pin "1") (pinfunction "1_1") (pintype "passive"))
      (node (ref "L9") (pin "2") (pinfunction "2_2") (pintype "passive"))
      (node (ref "U4") (pin "10") (pinfunction "BATT_10") (pintype "passive"))
      (node (ref "U4") (pin "9") (pinfunction "BATT_9") (pintype "passive"))
    )
    (net (code "59") (name "GND") (class "Default")
      (node (ref "C1") (pin "2") (pinfunction "2_2") (pintype "passive"))
      (node (ref "C12") (pin "2") (pinfunction "2_2") (pintype "passive"))
      (node (ref "C13") (pin "2") (pinfunction "2_2") (pintype "passive"))
      (node (ref "C14") (pin "2") (pinfunction "2_2") (pintype "passive"))
      (node (ref "C15") (pin "2") (pinfunction "2_2") (pintype "passive"))
      (node (ref "C16") (pin "2") (pinfunction "2_2") (pintype "passive"))
      (node (ref "C17") (pin "2") (pinfunction "2_2") (pintype "passive"))
      (node (ref "C19") (pin "2") (pinfunction "2_2") (pintype "passive"))
      (node (ref "C20") (pin "2") (pinfunction "2_2") (pintype "passive"))
      (node (ref "C21") (pin "2") (pinfunction "2_2") (pintype "passive"))
      (node (ref "C22") (pin "2") (pinfunction "2_2") (pintype "passive"))
      (node (ref "C23") (pin "2") (pinfunction "2_2") (pintype "passive"))
      (node (ref "C24") (pin "2") (pinfunction "2_2") (pintype "passive"))
      (node (ref "C25") (pin "2") (pinfunction "2_2") (pintype "passive"))
      (node (ref "C26") (pin "2") (pinfunction "2_2") (pintype "passive"))
      (node (ref "C27") (pin "2") (pinfunction "2_2") (pintype "passive"))
      (node (ref "C28") (pin "2") (pinfunction "2_2") (pintype "passive"))
      (node (ref "C29") (pin "2") (pinfunction "2_2") (pintype "passive"))
      (node (ref "C3") (pin "2") (pinfunction "2_2") (pintype "passive"))
      (node (ref "C30") (pin "2") (pinfunction "2_2") (pintype "passive"))
      (node (ref "C31") (pin "2") (pinfunction "2_2") (pintype "passive"))
      (node (ref "C32") (pin "2") (pinfunction "2_2") (pintype "passive"))
      (node (ref "C33") (pin "2") (pinfunction "2_2") (pintype "passive"))
      (node (ref "C34") (pin "1") (pinfunction "1_1") (pintype "passive"))
      (node (ref "C35") (pin "1") (pinfunction "1_1") (pintype "passive"))
      (node (ref "C36") (pin "1") (pinfunction "1_1") (pintype "passive"))
      (node (ref "C37") (pin "1") (pinfunction "1_1") (pintype "passive"))
      (node (ref "C38") (pin "1") (pinfunction "1_1") (pintype "passive"))
      (node (ref "C39") (pin "1") (pinfunction "1_1") (pintype "passive"))
      (node (ref "C4") (pin "2") (pinfunction "2_2") (pintype "passive"))
      (node (ref "C40") (pin "2") (pinfunction "2_2") (pintype "passive"))
      (node (ref "C41") (pin "2") (pinfunction "2_2") (pintype "passive"))
      (node (ref "C42") (pin "2") (pinfunction "2_2") (pintype "passive"))
      (node (ref "C43") (pin "2") (pinfunction "2_2") (pintype "passive"))
      (node (ref "C46") (pin "2") (pinfunction "2_2") (pintype "passive"))
      (node (ref "C47") (pin "2") (pinfunction "2_2") (pintype "passive"))
      (node (ref "C48") (pin "2") (pinfunction "2_2") (pintype "passive"))
      (node (ref "C49") (pin "1") (pinfunction "1_1") (pintype "passive"))
      (node (ref "C50") (pin "2") (pinfunction "2_2") (pintype "passive"))
      (node (ref "C51") (pin "2") (pinfunction "2_2") (pintype "passive"))
      (node (ref "C52") (pin "2") (pinfunction "2_2") (pintype "passive"))
      (node (ref "C53") (pin "2") (pinfunction "2_2") (pintype "passive"))
      (node (ref "C54") (pin "2") (pinfunction "2_2") (pintype "passive"))
      (node (ref "C55") (pin "2") (pinfunction "2_2") (pintype "passive"))
      (node (ref "C56") (pin "2") (pinfunction "2_2") (pintype "passive"))
      (node (ref "C57") (pin "2") (pinfunction "2_2") (pintype "passive"))
      (node (ref "C6") (pin "2") (pinfunction "2_2") (pintype "passive"))
      (node (ref "C8") (pin "2") (pinfunction "2_2") (pintype "passive"))
      (node (ref "C9") (pin "1") (pinfunction "1_1") (pintype "passive"))
      (node (ref "D1") (pin "1") (pinfunction "A_1") (pintype "passive"))
      (node (ref "D10") (pin "2") (pinfunction "K_2") (pintype "passive"))
      (node (ref "D11") (pin "2") (pinfunction "K_2") (pintype "passive"))
      (node (ref "D2") (pin "1") (pinfunction "A_1") (pintype "passive"))
      (node (ref "D4") (pin "1") (pinfunction "A_1") (pintype "passive"))
      (node (ref "D7") (pin "2") (pinfunction "K_2") (pintype "passive"))
      (node (ref "D8") (pin "2") (pinfunction "A_2") (pintype "passive"))
      (node (ref "J1") (pin "2") (pinfunction "2_2") (pintype "passive"))
      (node (ref "J5") (pin "3") (pinfunction "3_3") (pintype "passive"))
      (node (ref "J6") (pin "3") (pinfunction "3_3") (pintype "passive"))
      (node (ref "J7") (pin "3") (pinfunction "3_3") (pintype "passive"))
      (node (ref "JS1") (pin "2") (pinfunction "2_2") (pintype "passive"))
      (node (ref "JS1") (pin "B1") (pinfunction "B1_B1") (pintype "passive"))
      (node (ref "JS1") (pin "B2") (pinfunction "B2_B2") (pintype "passive"))
      (node (ref "Q2") (pin "3") (pinfunction "C_3") (pintype "passive"))
      (node (ref "Q6") (pin "3") (pinfunction "S_3") (pintype "passive"))
      (node (ref "Q7") (pin "3") (pinfunction "3_3") (pintype "passive"))
      (node (ref "R11") (pin "2") (pinfunction "2_2") (pintype "passive"))
      (node (ref "R19") (pin "2") (pinfunction "2_2") (pintype "passive"))
      (node (ref "R20") (pin "2") (pinfunction "2_2") (pintype "passive"))
      (node (ref "R27") (pin "2") (pinfunction "2_2") (pintype "passive"))
      (node (ref "R30") (pin "2") (pinfunction "2_2") (pintype "passive"))
      (node (ref "R34") (pin "2") (pinfunction "2_2") (pintype "passive"))
      (node (ref "R4") (pin "2") (pinfunction "2_2") (pintype "passive"))
      (node (ref "R48") (pin "2") (pinfunction "2_2") (pintype "passive"))
      (node (ref "R5") (pin "1") (pinfunction "1_1") (pintype "passive"))
      (node (ref "R59") (pin "2") (pinfunction "2_2") (pintype "passive"))
      (node (ref "R7") (pin "2") (pinfunction "2_2") (pintype "passive"))
      (node (ref "R8") (pin "2") (pinfunction "2_2") (pintype "passive"))
      (node (ref "TP8") (pin "1") (pinfunction "1_1") (pintype "passive"))
      (node (ref "U1") (pin "10") (pinfunction "GND_10") (pintype "passive"))
      (node (ref "U1") (pin "12") (pinfunction "GND_12") (pintype "passive"))
      (node (ref "U1") (pin "13") (pinfunction "GND_13") (pintype "passive"))
      (node (ref "U1") (pin "24") (pinfunction "GND_24") (pintype "passive"))
      (node (ref "U10") (pin "12") (pinfunction "VSSA_12") (pintype "passive"))
      (node (ref "U10") (pin "18") (pinfunction "VSS_4_18") (pintype "passive"))
      (node (ref "U10") (pin "28") (pinfunction "PB2/BOOT1_28") (pintype "passive"))
      (node (ref "U10") (pin "31") (pinfunction "VSS_1_31") (pintype "passive"))
      (node (ref "U10") (pin "47") (pinfunction "VSS_2_47") (pintype "passive"))
      (node (ref "U10") (pin "60") (pinfunction "BOOT0_60") (pintype "passive"))
      (node (ref "U10") (pin "63") (pinfunction "VSS_3_63") (pintype "passive"))
      (node (ref "U11") (pin "4") (pinfunction "GND_4") (pintype "passive"))
      (node (ref "U11") (pin "9") (pinfunction "PAD_9") (pintype "passive"))
      (node (ref "U12") (pin "2") (pinfunction "GND_2") (pintype "passive"))
      (node (ref "U13") (pin "1") (pinfunction "A0_1") (pintype "passive"))
      (node (ref "U13") (pin "2") (pinfunction "A1_2") (pintype "passive"))
      (node (ref "U13") (pin "3") (pinfunction "A2_3") (pintype "passive"))
      (node (ref "U13") (pin "4") (pinfunction "VSS_4") (pintype "power_in"))
      (node (ref "U13") (pin "7") (pinfunction "WP_7") (pintype "passive"))
      (node (ref "U2") (pin "5") (pinfunction "GND_5") (pintype "passive"))
      (node (ref "U2") (pin "9") (pinfunction "NC_9") (pintype "passive"))
      (node (ref "U3") (pin "2") (pinfunction "2_2") (pintype "passive"))
      (node (ref "U4") (pin "1") (pinfunction "GND_1") (pintype "passive"))
      (node (ref "U4") (pin "2") (pinfunction "GND_2") (pintype "passive"))
      (node (ref "U4") (pin "32") (pinfunction "GND_32") (pintype "passive"))
      (node (ref "U4") (pin "4") (pinfunction "GND_4") (pintype "passive"))
      (node (ref "U4") (pin "42") (pinfunction "GND_42") (pintype "passive"))
      (node (ref "U4") (pin "5") (pinfunction "GND_5") (pintype "passive"))
      (node (ref "U4") (pin "7") (pinfunction "GND_7") (pintype "passive"))
      (node (ref "U4") (pin "8") (pinfunction "GND_8") (pintype "passive"))
      (node (ref "U5") (pin "1") (pinfunction "TEMP_1") (pintype "passive"))
      (node (ref "U5") (pin "3") (pinfunction "GND_3") (pintype "passive"))
      (node (ref "U5") (pin "6") (pinfunction "~{STDB}Y_6") (pintype "passive"))
      (node (ref "U5") (pin "7") (pinfunction "~{CHR}G_7") (pintype "passive"))
      (node (ref "U5") (pin "9") (pinfunction "PAD_9") (pintype "passive"))
      (node (ref "U6") (pin "2") (pinfunction "GND_2") (pintype "passive"))
      (node (ref "U7") (pin "2") (pinfunction "GND_2") (pintype "passive"))
      (node (ref "U8") (pin "1") (pinfunction "VSS_1") (pintype "passive"))
      (node (ref "U9") (pin "2") (pinfunction "GND_2") (pintype "passive"))
    )
    (net (code "60") (name "Net-(ANT1-ANT)") (class "Default")
      (node (ref "ANT1") (pin "1") (pinfunction "ANT_1") (pintype "passive"))
      (node (ref "U1") (pin "11") (pinfunction "RF_IN_11") (pintype "passive"))
    )
    (net (code "61") (name "Net-(ANT2-Pad1)") (class "Default")
      (node (ref "ANT2") (pin "1") (pinfunction "1_1") (pintype "passive"))
      (node (ref "C56") (pin "1") (pinfunction "1_1") (pintype "passive"))
      (node (ref "R68") (pin "2") (pinfunction "2_2") (pintype "passive"))
    )
    (net (code "62") (name "Net-(C5-Pad2)") (class "Default")
      (node (ref "C5") (pin "2") (pinfunction "2_2") (pintype "passive"))
      (node (ref "R5") (pin "2") (pinfunction "2_2") (pintype "passive"))
    )
    (net (code "63") (name "Net-(C14-Pad1)") (class "Default")
      (node (ref "C14") (pin "1") (pinfunction "1_1") (pintype "passive"))
      (node (ref "R10") (pin "2") (pinfunction "2_2") (pintype "passive"))
    )
    (net (code "64") (name "Net-(C18-Pad2)") (class "Default")
      (node (ref "C18") (pin "2") (pinfunction "2_2") (pintype "passive"))
      (node (ref "C40") (pin "1") (pinfunction "1_1") (pintype "passive"))
    )
    (net (code "65") (name "Net-(C54-Pad1)") (class "Default")
      (node (ref "C54") (pin "1") (pinfunction "1_1") (pintype "passive"))
      (node (ref "R67") (pin "1") (pinfunction "1_1") (pintype "passive"))
      (node (ref "R7") (pin "1") (pinfunction "1_1") (pintype "passive"))
      (node (ref "U3") (pin "3") (pinfunction "3_3") (pintype "passive"))
    )
    (net (code "66") (name "Net-(D1-K)") (class "Default")
      (node (ref "D1") (pin "2") (pinfunction "K_2") (pintype "passive"))
      (node (ref "R2") (pin "1") (pinfunction "1_1") (pintype "passive"))
      (node (ref "U3") (pin "1") (pinfunction "1_1") (pintype "passive"))
    )
    (net (code "67") (name "Net-(D2-K)") (class "Default")
      (node (ref "C2") (pin "2") (pinfunction "2_2") (pintype "passive"))
      (node (ref "D2") (pin "2") (pinfunction "K_2") (pintype "passive"))
      (node (ref "L1") (pin "1") (pinfunction "1_1") (pintype "passive"))
      (node (ref "U2") (pin "1") (pinfunction "SW_1") (pintype "passive"))
    )
    (net (code "68") (name "Net-(D3-A)") (class "Default")
      (node (ref "C18") (pin "1") (pinfunction "1_1") (pintype "passive"))
      (node (ref "D3") (pin "1") (pinfunction "A_1") (pintype "passive"))
      (node (ref "J1") (pin "1") (pinfunction "1_1") (pintype "passive"))
    )
    (net (code "69") (name "Net-(D3-K)") (class "Default")
      (node (ref "D3") (pin "2") (pinfunction "K_2") (pintype "passive"))
      (node (ref "F1") (pin "1") (pinfunction "1_1") (pintype "passive"))
    )
    (net (code "70") (name "Net-(D7-A)") (class "Default")
      (node (ref "D7") (pin "1") (pinfunction "A_1") (pintype "passive"))
      (node (ref "R25") (pin "2") (pinfunction "2_2") (pintype "passive"))
    )
    (net (code "71") (name "Net-(D10-A)") (class "Default")
      (node (ref "D10") (pin "1") (pinfunction "A_1") (pintype "passive"))
      (node (ref "R37") (pin "2") (pinfunction "2_2") (pintype "passive"))
    )
    (net (code "72") (name "Net-(D11-A)") (class "Default")
      (node (ref "D11") (pin "1") (pinfunction "A_1") (pintype "passive"))
      (node (ref "R38") (pin "1") (pinfunction "1_1") (pintype "passive"))
    )
    (net (code "73") (name "Net-(Q1-B)") (class "Default")
      (node (ref "Q1") (pin "2") (pinfunction "B_2") (pintype "passive"))
      (node (ref "Q2") (pin "1") (pinfunction "E_1") (pintype "passive"))
      (node (ref "R11") (pin "1") (pinfunction "1_1") (pintype "passive"))
    )
    (net (code "74") (name "Net-(Q1-C)") (class "Default")
      (node (ref "Q1") (pin "3") (pinfunction "C_3") (pintype "passive"))
      (node (ref "R60") (pin "1") (pinfunction "1_1") (pintype "passive"))
    )
    (net (code "75") (name "Net-(Q1-E)") (class "Default")
      (node (ref "Q1") (pin "1") (pinfunction "E_1") (pintype "passive"))
      (node (ref "R9") (pin "2") (pinfunction "2_2") (pintype "passive"))
    )
    (net (code "76") (name "Net-(Q3-G)") (class "Default")
      (node (ref "C41") (pin "1") (pinfunction "1_1") (pintype "passive"))
      (node (ref "Q3") (pin "1") (pinfunction "G_1") (pintype "passive"))
      (node (ref "R13") (pin "2") (pinfunction "2_2") (pintype "passive"))
      (node (ref "R29") (pin "1") (pinfunction "1_1") (pintype "passive"))
      (node (ref "TP9") (pin "1") (pinfunction "1_1") (pintype "passive"))
    )
    (net (code "77") (name "Net-(Q5-G)") (class "Default")
      (node (ref "Q5") (pin "1") (pinfunction "G_1") (pintype "passive"))
      (node (ref "R35") (pin "2") (pinfunction "2_2") (pintype "passive"))
    )
    (net (code "78") (name "Net-(Q5-S)") (class "Default")
      (node (ref "L9") (pin "1") (pinfunction "1_1") (pintype "passive"))
      (node (ref "Q5") (pin "3") (pinfunction "S_3") (pintype "passive"))
      (node (ref "R56") (pin "1") (pinfunction "1_1") (pintype "passive"))
      (node (ref "TP11") (pin "1") (pinfunction "1_1") (pintype "passive"))
    )
    (net (code "79") (name "Net-(Q6-D)") (class "Default")
      (node (ref "Q6") (pin "2") (pinfunction "D_2") (pintype "passive"))
      (node (ref "R56") (pin "2") (pinfunction "2_2") (pintype "passive"))
    )
    (net (code "80") (name "Net-(Q6-G)") (class "Default")
      (node (ref "C48") (pin "1") (pinfunction "1_1") (pintype "passive"))
      (node (ref "Q6") (pin "1") (pinfunction "G_1") (pintype "passive"))
      (node (ref "R36") (pin "1") (pinfunction "1_1") (pintype "passive"))
    )
    (net (code "81") (name "Net-(R22-Pad1)") (class "Default")
      (node (ref "R22") (pin "1") (pinfunction "1_1") (pintype "passive"))
      (node (ref "R23") (pin "2") (pinfunction "2_2") (pintype "passive"))
      (node (ref "R27") (pin "1") (pinfunction "1_1") (pintype "passive"))
    )
    (net (code "82") (name "Net-(U1-RX1)") (class "Default")
      (node (ref "R41") (pin "2") (pinfunction "2_2") (pintype "passive"))
      (node (ref "U1") (pin "21") (pinfunction "RX1_21") (pintype "passive"))
    )
    (net (code "83") (name "Net-(U1-TX1)") (class "Default")
      (node (ref "R40") (pin "2") (pinfunction "2_2") (pintype "passive"))
      (node (ref "U1") (pin "20") (pinfunction "TX1_20") (pintype "passive"))
    )
    (net (code "84") (name "Net-(U1-VBACK)") (class "Default")
      (node (ref "R1") (pin "2") (pinfunction "2_2") (pintype "passive"))
      (node (ref "U1") (pin "22") (pinfunction "VBACK_22") (pintype "passive"))
    )
    (net (code "85") (name "Net-(U1-VCC_RF)") (class "Default")
      (node (ref "R26") (pin "1") (pinfunction "1_1") (pintype "passive"))
      (node (ref "U1") (pin "9") (pinfunction "VCC_RF_9") (pintype "passive"))
    )
    (net (code "86") (name "Net-(U1-V_ANT)") (class "Default")
      (node (ref "R26") (pin "2") (pinfunction "2_2") (pintype "passive"))
      (node (ref "U1") (pin "8") (pinfunction "V_ANT_8") (pintype "passive"))
    )
    (net (code "87") (name "Net-(U1-nRESET)") (class "Default")
      (node (ref "R66") (pin "2") (pinfunction "2_2") (pintype "passive"))
      (node (ref "U1") (pin "1") (pinfunction "nRESET_1") (pintype "passive"))
    )
    (net (code "88") (name "Net-(U2-BST)") (class "Default")
      (node (ref "C2") (pin "1") (pinfunction "1_1") (pintype "passive"))
      (node (ref "U2") (pin "8") (pinfunction "BST_8") (pintype "passive"))
    )
    (net (code "89") (name "Net-(U2-COMP)") (class "Default")
      (node (ref "C5") (pin "1") (pinfunction "1_1") (pintype "passive"))
      (node (ref "U2") (pin "3") (pinfunction "COMP_3") (pintype "passive"))
    )
    (net (code "90") (name "Net-(U2-FB)") (class "Default")
      (node (ref "C13") (pin "1") (pinfunction "1_1") (pintype "passive"))
      (node (ref "R6") (pin "2") (pinfunction "2_2") (pintype "passive"))
      (node (ref "R8") (pin "1") (pinfunction "1_1") (pintype "passive"))
      (node (ref "U2") (pin "4") (pinfunction "FB_4") (pintype "passive"))
    )
    (net (code "91") (name "Net-(U2-FREQ)") (class "Default")
      (node (ref "R4") (pin "1") (pinfunction "1_1") (pintype "passive"))
      (node (ref "U2") (pin "6") (pinfunction "FREQ_6") (pintype "passive"))
    )
    (net (code "92") (name "Net-(U2-VIN)") (class "Default")
      (node (ref "C6") (pin "1") (pinfunction "1_1") (pintype "passive"))
      (node (ref "C8") (pin "1") (pinfunction "1_1") (pintype "passive"))
      (node (ref "C9") (pin "2") (pinfunction "2_2") (pintype "passive"))
      (node (ref "L2") (pin "2") (pinfunction "2_2") (pintype "passive"))
      (node (ref "U2") (pin "7") (pinfunction "VIN_7") (pintype "passive"))
    )
    (net (code "93") (name "Net-(U4-EMERG_RST)") (class "Default")
      (node (ref "R24") (pin "1") (pinfunction "1_1") (pintype "passive"))
      (node (ref "U4") (pin "37") (pinfunction "EMERG_RST_37") (pintype "passive"))
    )
    (net (code "94") (name "Net-(U4-HST_RXD)") (class "Default")
      (node (ref "J5") (pin "2") (pinfunction "2_2") (pintype "passive"))
      (node (ref "U4") (pin "11") (pinfunction "HST_RXD_11") (pintype "passive"))
    )
    (net (code "95") (name "Net-(U4-HST_TXD)") (class "Default")
      (node (ref "J5") (pin "1") (pinfunction "1_1") (pintype "passive"))
      (node (ref "U4") (pin "12") (pinfunction "HST_TXD_12") (pintype "passive"))
    )
    (net (code "96") (name "Net-(U4-POWER_ON)") (class "Default")
      (node (ref "R21") (pin "1") (pinfunction "1_1") (pintype "passive"))
      (node (ref "U4") (pin "14") (pinfunction "POWER_ON_14") (pintype "passive"))
    )
    (net (code "97") (name "Net-(U4-RF_ANT)") (class "Default")
      (node (ref "C57") (pin "1") (pinfunction "1_1") (pintype "passive"))
      (node (ref "R68") (pin "1") (pinfunction "1_1") (pintype "passive"))
      (node (ref "U4") (pin "3") (pinfunction "RF_ANT_3") (pintype "passive"))
    )
    (net (code "98") (name "Net-(U4-SIM_CD)") (class "Default")
      (node (ref "R18") (pin "2") (pintype "passive"))
      (node (ref "U4") (pin "27") (pinfunction "SIM_CD_27") (pintype "passive"))
    )
    (net (code "99") (name "Net-(U4-SIM_CLK)") (class "Default")
      (node (ref "R16") (pin "1") (pinfunction "1_1") (pintype "passive"))
      (node (ref "U4") (pin "24") (pinfunction "SIM_CLK_24") (pintype "passive"))
    )
    (net (code "100") (name "Net-(U4-SIM_DATA)") (class "Default")
      (node (ref "R14") (pin "1") (pinfunction "1_1") (pintype "passive"))
      (node (ref "U4") (pin "23") (pinfunction "SIM_DATA_23") (pintype "passive"))
    )
    (net (code "101") (name "Net-(U4-SIM_RST)") (class "Default")
      (node (ref "R17") (pin "1") (pinfunction "1_1") (pintype "passive"))
      (node (ref "U4") (pin "25") (pinfunction "SIM_RST_25") (pintype "passive"))
    )
    (net (code "102") (name "Net-(U4-WAKE_UP)") (class "Default")
      (node (ref "R12") (pin "2") (pinfunction "2_2") (pintype "passive"))
      (node (ref "R51") (pin "1") (pinfunction "1_1") (pintype "passive"))
      (node (ref "U4") (pin "41") (pinfunction "WAKE_UP_41") (pintype "passive"))
    )
    (net (code "103") (name "Net-(U5-PROG)") (class "Default")
      (node (ref "R19") (pin "1") (pinfunction "1_1") (pintype "passive"))
      (node (ref "U5") (pin "2") (pinfunction "PROG_2") (pintype "passive"))
    )
    (net (code "104") (name "Net-(U9-CANH)") (class "Default")
      (node (ref "Q7") (pin "1") (pinfunction "1_1") (pintype "passive"))
      (node (ref "R39") (pin "1") (pinfunction "1_1") (pintype "passive"))
      (node (ref "R42") (pin "1") (pinfunction "1_1") (pintype "passive"))
      (node (ref "U9") (pin "7") (pinfunction "CANH_7") (pintype "passive"))
    )
    (net (code "105") (name "Net-(U9-CANL)") (class "Default")
      (node (ref "Q7") (pin "2") (pinfunction "2_2") (pintype "passive"))
      (node (ref "R42") (pin "2") (pinfunction "2_2") (pintype "passive"))
      (node (ref "R43") (pin "1") (pinfunction "1_1") (pintype "passive"))
      (node (ref "U9") (pin "6") (pinfunction "CANL_6") (pintype "passive"))
    )
    (net (code "106") (name "Net-(U9-RXD)") (class "Default")
      (node (ref "R58") (pin "1") (pinfunction "1_1") (pintype "passive"))
      (node (ref "U9") (pin "4") (pinfunction "RXD_4") (pintype "passive"))
    )
    (net (code "107") (name "Net-(U9-TXD)") (class "Default")
      (node (ref "R57") (pin "1") (pinfunction "1_1") (pintype "passive"))
      (node (ref "U9") (pin "1") (pinfunction "TXD_1") (pintype "passive"))
    )
    (net (code "108") (name "Net-(U10-VDDA)") (class "Default")
      (node (ref "C55") (pin "1") (pinfunction "1_1") (pintype "passive"))
      (node (ref "R61") (pin "1") (pinfunction "1_1") (pintype "passive"))
      (node (ref "U10") (pin "13") (pinfunction "VDDA_13") (pintype "passive"))
    )
    (net (code "109") (name "Net-(U11-CLK)") (class "Default")
      (node (ref "R64") (pin "1") (pinfunction "1_1") (pintype "passive"))
      (node (ref "U11") (pin "6") (pinfunction "CLK_6") (pintype "passive"))
    )
    (net (code "110") (name "Net-(U11-DI{slash}IO0)") (class "Default")
      (node (ref "R65") (pin "1") (pinfunction "1_1") (pintype "passive"))
      (node (ref "U11") (pin "5") (pinfunction "DI/IO0_5") (pintype "passive"))
    )
    (net (code "111") (name "Net-(U11-DO{slash}IO1)") (class "Default")
      (node (ref "R63") (pin "2") (pinfunction "2_2") (pintype "passive"))
      (node (ref "U11") (pin "2") (pinfunction "DO/IO1_2") (pintype "passive"))
    )
    (net (code "112") (name "Net-(U11-~{CS})") (class "Default")
      (node (ref "R62") (pin "2") (pinfunction "2_2") (pintype "passive"))
      (node (ref "U11") (pin "1") (pinfunction "~{CS}_1") (pintype "passive"))
    )
    (net (code "113") (name "Net-(Y2-OSC1)") (class "Default")
      (node (ref "C38") (pin "2") (pinfunction "2_2") (pintype "passive"))
      (node (ref "R46") (pin "1") (pinfunction "1_1") (pintype "passive"))
      (node (ref "Y2") (pin "1") (pinfunction "OSC1_1") (pintype "passive"))
    )
    (net (code "114") (name "unconnected-(U1-1PPS-Pad3)") (class "Default")
      (node (ref "U1") (pin "3") (pinfunction "1PPS_3") (pintype "passive"))
    )
    (net (code "115") (name "unconnected-(U1-NC-Pad2)") (class "Default")
      (node (ref "U1") (pin "2") (pinfunction "NC_2") (pintype "passive"))
    )
    (net (code "116") (name "unconnected-(U1-NC-Pad4)") (class "Default")
      (node (ref "U1") (pin "4") (pinfunction "NC_4") (pintype "passive"))
    )
    (net (code "117") (name "unconnected-(U1-NC-Pad5)") (class "Default")
      (node (ref "U1") (pin "5") (pinfunction "NC_5") (pintype "passive"))
    )
    (net (code "118") (name "unconnected-(U1-NC-Pad6)") (class "Default")
      (node (ref "U1") (pin "6") (pinfunction "NC_6") (pintype "passive"))
    )
    (net (code "119") (name "unconnected-(U1-NC-Pad7)") (class "Default")
      (node (ref "U1") (pin "7") (pinfunction "NC_7") (pintype "passive"))
    )
    (net (code "120") (name "unconnected-(U1-NC-Pad14)") (class "Default")
      (node (ref "U1") (pin "14") (pinfunction "NC_14") (pintype "passive"))
    )
    (net (code "121") (name "unconnected-(U1-NC-Pad15)") (class "Default")
      (node (ref "U1") (pin "15") (pinfunction "NC_15") (pintype "passive"))
    )
    (net (code "122") (name "unconnected-(U1-NC-Pad16)") (class "Default")
      (node (ref "U1") (pin "16") (pinfunction "NC_16") (pintype "passive"))
    )
    (net (code "123") (name "unconnected-(U1-PWR_DWN-Pad17)") (class "Default")
      (node (ref "U1") (pin "17") (pinfunction "PWR_DWN_17") (pintype "passive"))
    )
    (net (code "124") (name "unconnected-(U1-RX2-Pad19)") (class "Default")
      (node (ref "U1") (pin "19") (pinfunction "RX2_19") (pintype "passive"))
    )
    (net (code "125") (name "unconnected-(U1-TX2-Pad18)") (class "Default")
      (node (ref "U1") (pin "18") (pinfunction "TX2_18") (pintype "passive"))
    )
    (net (code "126") (name "unconnected-(U2-EN-Pad2)") (class "Default")
      (node (ref "U2") (pin "2") (pinfunction "EN_2") (pintype "passive"))
    )
    (net (code "127") (name "unconnected-(U4-AUXI+-Pad29)") (class "Default")
      (node (ref "U4") (pin "29") (pinfunction "AUXI+_29") (pintype "passive"))
    )
    (net (code "128") (name "unconnected-(U4-AUXI--Pad28)") (class "Default")
      (node (ref "U4") (pin "28") (pinfunction "AUXI-_28") (pintype "passive"))
    )
    (net (code "129") (name "unconnected-(U4-AUXO+-Pad35)") (class "Default")
      (node (ref "U4") (pin "35") (pinfunction "AUXO+_35") (pintype "passive"))
    )
    (net (code "130") (name "unconnected-(U4-AUXO--Pad36)") (class "Default")
      (node (ref "U4") (pin "36") (pinfunction "AUXO-_36") (pintype "passive"))
    )
    (net (code "131") (name "unconnected-(U4-EAR+-Pad33)") (class "Default")
      (node (ref "U4") (pin "33") (pinfunction "EAR+_33") (pintype "passive"))
    )
    (net (code "132") (name "unconnected-(U4-EAR--Pad34)") (class "Default")
      (node (ref "U4") (pin "34") (pinfunction "EAR-_34") (pintype "passive"))
    )
    (net (code "133") (name "unconnected-(U4-LPG-Pad38)") (class "Default")
      (node (ref "U4") (pin "38") (pinfunction "LPG_38") (pintype "passive"))
    )
    (net (code "134") (name "unconnected-(U4-MIC+-Pad31)") (class "Default")
      (node (ref "U4") (pin "31") (pinfunction "MIC+_31") (pintype "passive"))
    )
    (net (code "135") (name "unconnected-(U4-MIC--Pad30)") (class "Default")
      (node (ref "U4") (pin "30") (pinfunction "MIC-_30") (pintype "passive"))
    )
    (net (code "136") (name "unconnected-(U4-UART1_CTS-Pad21)") (class "Default")
      (node (ref "U4") (pin "21") (pinfunction "UART1_CTS_21") (pintype "passive"))
    )
    (net (code "137") (name "unconnected-(U4-UART1_DCD-Pad17)") (class "Default")
      (node (ref "U4") (pin "17") (pinfunction "UART1_DCD_17") (pintype "passive"))
    )
    (net (code "138") (name "unconnected-(U4-UART1_DSR-Pad16)") (class "Default")
      (node (ref "U4") (pin "16") (pinfunction "UART1_DSR_16") (pintype "passive"))
    )
    (net (code "139") (name "unconnected-(U4-UART1_DTR-Pad15)") (class "Default")
      (node (ref "U4") (pin "15") (pinfunction "UART1_DTR_15") (pintype "passive"))
    )
    (net (code "140") (name "unconnected-(U4-UART1_RING-Pad22)") (class "Default")
      (node (ref "U4") (pin "22") (pinfunction "UART1_RING_22") (pintype "passive"))
    )
    (net (code "141") (name "unconnected-(U4-UART1_RTS-Pad20)") (class "Default")
      (node (ref "U4") (pin "20") (pinfunction "UART1_RTS_20") (pintype "passive"))
    )
    (net (code "142") (name "unconnected-(U4-UART2_RXD-Pad39)") (class "Default")
      (node (ref "U4") (pin "39") (pinfunction "UART2_RXD_39") (pintype "passive"))
    )
    (net (code "143") (name "unconnected-(U4-UART2_TXD-Pad40)") (class "Default")
      (node (ref "U4") (pin "40") (pinfunction "UART2_TXD_40") (pintype "passive"))
    )
    (net (code "144") (name "unconnected-(U4-VBACKUP-Pad6)") (class "Default")
      (node (ref "U4") (pin "6") (pinfunction "VBACKUP_6") (pintype "passive"))
    )
    (net (code "145") (name "unconnected-(U6-NC-Pad4)") (class "Default")
      (node (ref "U6") (pin "4") (pinfunction "NC_4") (pintype "passive"))
    )
    (net (code "146") (name "unconnected-(U7-NC-Pad4)") (class "Default")
      (node (ref "U7") (pin "4") (pinfunction "NC_4") (pintype "passive"))
    )
    (net (code "147") (name "unconnected-(U8-NC-Pad4)") (class "Default")
      (node (ref "U8") (pin "4") (pinfunction "NC_4") (pintype "passive"))
    )
    (net (code "148") (name "unconnected-(U8-NC-Pad5)") (class "Default")
      (node (ref "U8") (pin "5") (pinfunction "NC_5") (pintype "passive"))
    )
    (net (code "149") (name "unconnected-(U10-I2C1_SCL{slash}PB6-Pad58)") (class "Default")
      (node (ref "U10") (pin "58") (pinfunction "I2C1_SCL/PB6_58") (pintype "passive"))
    )
    (net (code "150") (name "unconnected-(U10-I2C1_SDA{slash}PB7-Pad59)") (class "Default")
      (node (ref "U10") (pin "59") (pinfunction "I2C1_SDA/PB7_59") (pintype "passive"))
    )
    (net (code "151") (name "unconnected-(U10-PA1-Pad15)") (class "Default")
      (node (ref "U10") (pin "15") (pinfunction "PA1_15") (pintype "passive"))
    )
    (net (code "152") (name "unconnected-(U10-PA8-Pad41)") (class "Default")
      (node (ref "U10") (pin "41") (pinfunction "PA8_41") (pintype "passive"))
    )
    (net (code "153") (name "unconnected-(U10-PB1-Pad27)") (class "Default")
      (node (ref "U10") (pin "27") (pinfunction "PB1_27") (pintype "passive"))
    )
    (net (code "154") (name "unconnected-(U10-PB8-Pad61)") (class "Default")
      (node (ref "U10") (pin "61") (pinfunction "PB8_61") (pintype "passive"))
    )
    (net (code "155") (name "unconnected-(U10-PB15-Pad36)") (class "Default")
      (node (ref "U10") (pin "36") (pinfunction "PB15_36") (pintype "passive"))
    )
    (net (code "156") (name "unconnected-(U10-PC3-Pad11)") (class "Default")
      (node (ref "U10") (pin "11") (pinfunction "PC3_11") (pintype "passive"))
    )
    (net (code "157") (name "unconnected-(U10-PC5-Pad25)") (class "Default")
      (node (ref "U10") (pin "25") (pinfunction "PC5_25") (pintype "passive"))
    )
    (net (code "158") (name "unconnected-(U10-PC6-Pad37)") (class "Default")
      (node (ref "U10") (pin "37") (pinfunction "PC6_37") (pintype "passive"))
    )
    (net (code "159") (name "unconnected-(U10-PC12-Pad53)") (class "Default")
      (node (ref "U10") (pin "53") (pinfunction "PC12_53") (pintype "passive"))
    )
    (net (code "160") (name "unconnected-(U10-PC13-TAMPER-RTC-Pad2)") (class "Default")
      (node (ref "U10") (pin "2") (pinfunction "PC13-TAMPER-RTC_2") (pintype "passive"))
    )
    (net (code "161") (name "unconnected-(U12-NC-Pad4)") (class "Default")
      (node (ref "U12") (pin "4") (pinfunction "NC_4") (pintype "passive"))
    )
  )
)
